# BlackIce.net
KiCad netlist of a schematic drawn in EAGLE
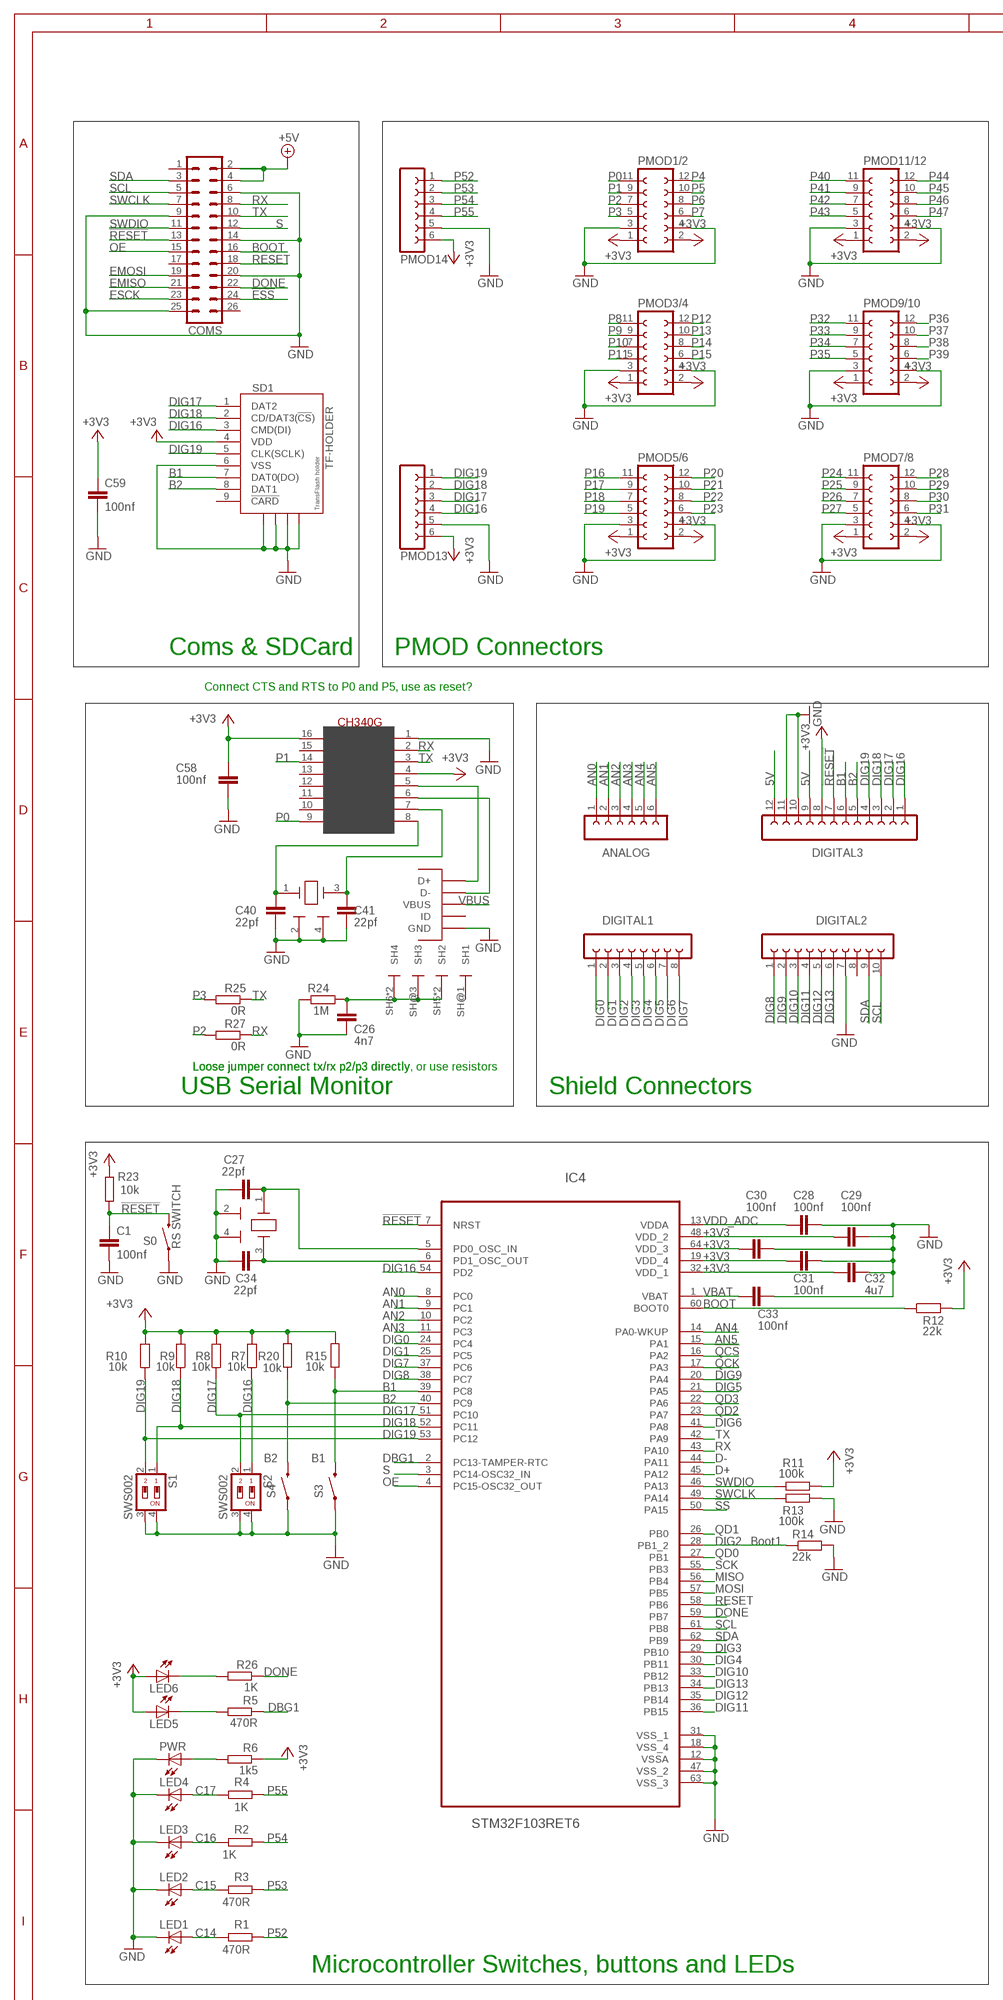
[diagram p0: schematic, sheet 1, part 1 of 2]
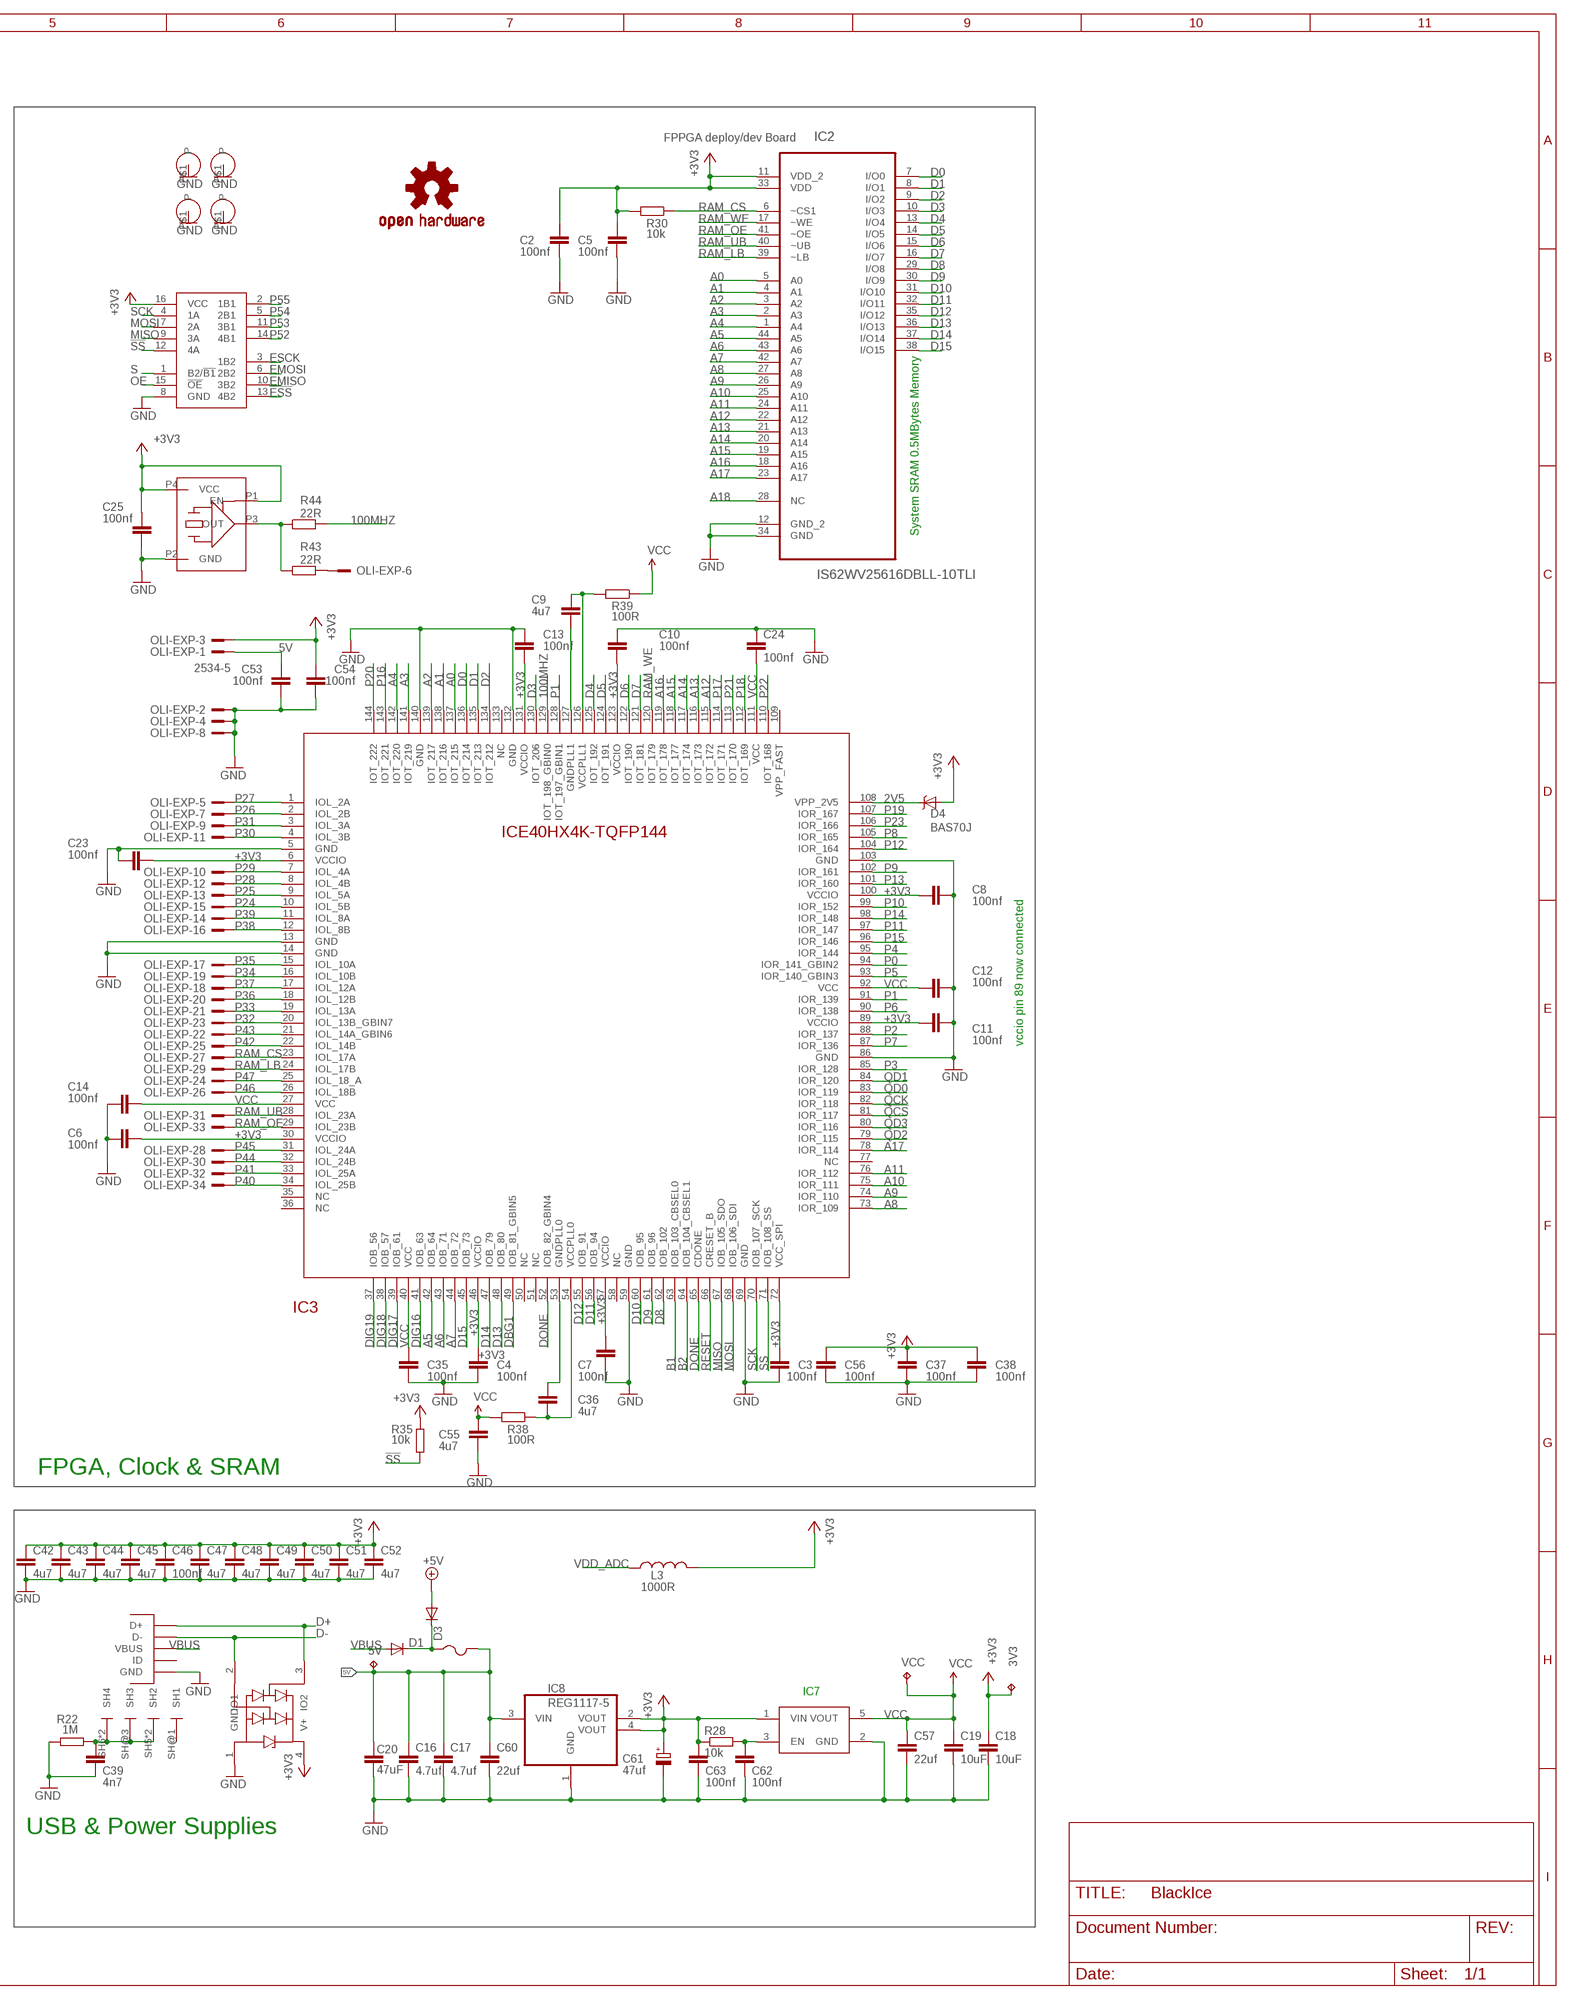
[diagram p1: schematic, sheet 1, part 2 of 2]

(export (version "E")
  (design (tool "Eeschema 10.0.6"))
  (components
    (comp (ref "3V3")
      (value "TPB1,27")
      (footprint "eagle-import:B1,27")
      (libsource (lib "eagle-import") (part "TPB1,27"))
    )
    (comp (ref "5V")
      (value "TPB1,27")
      (footprint "eagle-import:B1,27")
      (libsource (lib "eagle-import") (part "TPB1,27"))
    )
    (comp (ref "ANALOG")
      (value "FE06-1")
      (footprint "eagle-import:FE06")
      (libsource (lib "eagle-import") (part "FE06-1"))
    )
    (comp (ref "C1")
      (value "100nf")
      (footprint "eagle-import:C0402")
      (libsource (lib "eagle-import") (part "C-EUC0402"))
    )
    (comp (ref "C2")
      (value "100nf")
      (footprint "eagle-import:C0402")
      (libsource (lib "eagle-import") (part "C-EUC0402"))
    )
    (comp (ref "C3")
      (value "100nf")
      (footprint "eagle-import:C0402")
      (libsource (lib "eagle-import") (part "C-EUC0402"))
    )
    (comp (ref "C4")
      (value "100nf")
      (footprint "eagle-import:C0402")
      (libsource (lib "eagle-import") (part "C-EUC0402"))
    )
    (comp (ref "C5")
      (value "100nf")
      (footprint "eagle-import:C0402")
      (libsource (lib "eagle-import") (part "C-EUC0402"))
    )
    (comp (ref "C6")
      (value "100nf")
      (footprint "eagle-import:C0402")
      (libsource (lib "eagle-import") (part "C-EUC0402"))
    )
    (comp (ref "C7")
      (value "100nf")
      (footprint "eagle-import:C0402")
      (libsource (lib "eagle-import") (part "C-EUC0402"))
    )
    (comp (ref "C8")
      (value "100nf")
      (footprint "eagle-import:C0402")
      (libsource (lib "eagle-import") (part "C-EUC0402"))
    )
    (comp (ref "C9")
      (value "4u7")
      (footprint "eagle-import:C0402")
      (libsource (lib "eagle-import") (part "C-EUC0402"))
    )
    (comp (ref "C10")
      (value "100nf")
      (footprint "eagle-import:C0402")
      (libsource (lib "eagle-import") (part "C-EUC0402"))
    )
    (comp (ref "C11")
      (value "100nf")
      (footprint "eagle-import:C0402")
      (libsource (lib "eagle-import") (part "C-EUC0402"))
    )
    (comp (ref "C12")
      (value "100nf")
      (footprint "eagle-import:C0402")
      (libsource (lib "eagle-import") (part "C-EUC0402"))
    )
    (comp (ref "C13")
      (value "100nf")
      (footprint "eagle-import:C0402")
      (libsource (lib "eagle-import") (part "C-EUC0402"))
    )
    (comp (ref "C14")
      (value "100nf")
      (footprint "eagle-import:C0402")
      (libsource (lib "eagle-import") (part "C-EUC0402"))
    )
    (comp (ref "C16")
      (value "4.7uf")
      (footprint "eagle-import:C0402")
      (libsource (lib "eagle-import") (part "C-EUC0402"))
    )
    (comp (ref "C17")
      (value "4.7uf")
      (footprint "eagle-import:C0402")
      (libsource (lib "eagle-import") (part "C-EUC0402"))
    )
    (comp (ref "C18")
      (value "10uF")
      (footprint "eagle-import:C0603")
      (libsource (lib "eagle-import") (part "C-EUC0603"))
    )
    (comp (ref "C19")
      (value "10uF")
      (footprint "eagle-import:C0603")
      (libsource (lib "eagle-import") (part "C-EUC0603"))
    )
    (comp (ref "C20")
      (value "47uF")
      (footprint "eagle-import:1206")
      (libsource (lib "eagle-import") (part "C_1206"))
    )
    (comp (ref "C23")
      (value "100nf")
      (footprint "eagle-import:C0402")
      (libsource (lib "eagle-import") (part "C-EUC0402"))
    )
    (comp (ref "C24")
      (value "100nf")
      (footprint "eagle-import:C0402")
      (libsource (lib "eagle-import") (part "C-EUC0402"))
    )
    (comp (ref "C25")
      (value "100nf")
      (footprint "eagle-import:C0402")
      (libsource (lib "eagle-import") (part "C-EUC0402"))
    )
    (comp (ref "C26")
      (value "4n7")
      (footprint "eagle-import:C0402")
      (libsource (lib "eagle-import") (part "C-EUC0402"))
    )
    (comp (ref "C27")
      (value "22pf")
      (footprint "eagle-import:C0402")
      (libsource (lib "eagle-import") (part "C-EUC0402"))
    )
    (comp (ref "C28")
      (value "100nf")
      (footprint "eagle-import:C0402")
      (libsource (lib "eagle-import") (part "C-EUC0402"))
    )
    (comp (ref "C29")
      (value "100nf")
      (footprint "eagle-import:C0402")
      (libsource (lib "eagle-import") (part "C-EUC0402"))
    )
    (comp (ref "C30")
      (value "100nf")
      (footprint "eagle-import:C0402")
      (libsource (lib "eagle-import") (part "C-EUC0402"))
    )
    (comp (ref "C31")
      (value "100nf")
      (footprint "eagle-import:C0402")
      (libsource (lib "eagle-import") (part "C-EUC0402"))
    )
    (comp (ref "C32")
      (value "4u7")
      (footprint "eagle-import:C0402")
      (libsource (lib "eagle-import") (part "C-EUC0402"))
    )
    (comp (ref "C33")
      (value "100nf")
      (footprint "eagle-import:C0402")
      (libsource (lib "eagle-import") (part "C-EUC0402"))
    )
    (comp (ref "C34")
      (value "22pf")
      (footprint "eagle-import:C0402")
      (libsource (lib "eagle-import") (part "C-EUC0402"))
    )
    (comp (ref "C35")
      (value "100nf")
      (footprint "eagle-import:C0402")
      (libsource (lib "eagle-import") (part "C-EUC0402"))
    )
    (comp (ref "C36")
      (value "4u7")
      (footprint "eagle-import:C0402")
      (libsource (lib "eagle-import") (part "C-EUC0402"))
    )
    (comp (ref "C37")
      (value "100nf")
      (footprint "eagle-import:C0402")
      (libsource (lib "eagle-import") (part "C-EUC0402"))
    )
    (comp (ref "C38")
      (value "100nf")
      (footprint "eagle-import:C0402")
      (libsource (lib "eagle-import") (part "C-EUC0402"))
    )
    (comp (ref "C39")
      (value "4n7")
      (footprint "eagle-import:C0402")
      (libsource (lib "eagle-import") (part "C-EUC0402"))
    )
    (comp (ref "C40")
      (value "22pf")
      (footprint "eagle-import:C0402")
      (libsource (lib "eagle-import") (part "C-EUC0402"))
    )
    (comp (ref "C41")
      (value "22pf")
      (footprint "eagle-import:C0402")
      (libsource (lib "eagle-import") (part "C-EUC0402"))
    )
    (comp (ref "C42")
      (value "4u7")
      (footprint "eagle-import:C0402")
      (libsource (lib "eagle-import") (part "C-EUC0402"))
    )
    (comp (ref "C43")
      (value "4u7")
      (footprint "eagle-import:C0402")
      (libsource (lib "eagle-import") (part "C-EUC0402"))
    )
    (comp (ref "C44")
      (value "4u7")
      (footprint "eagle-import:C0402")
      (libsource (lib "eagle-import") (part "C-EUC0402"))
    )
    (comp (ref "C45")
      (value "4u7")
      (footprint "eagle-import:C0402")
      (libsource (lib "eagle-import") (part "C-EUC0402"))
    )
    (comp (ref "C46")
      (value "100nf")
      (footprint "eagle-import:C0402")
      (libsource (lib "eagle-import") (part "C-EUC0402"))
    )
    (comp (ref "C47")
      (value "4u7")
      (footprint "eagle-import:C0402")
      (libsource (lib "eagle-import") (part "C-EUC0402"))
    )
    (comp (ref "C48")
      (value "4u7")
      (footprint "eagle-import:C0402")
      (libsource (lib "eagle-import") (part "C-EUC0402"))
    )
    (comp (ref "C49")
      (value "4u7")
      (footprint "eagle-import:C0402")
      (libsource (lib "eagle-import") (part "C-EUC0402"))
    )
    (comp (ref "C50")
      (value "4u7")
      (footprint "eagle-import:C0402")
      (libsource (lib "eagle-import") (part "C-EUC0402"))
    )
    (comp (ref "C51")
      (value "4u7")
      (footprint "eagle-import:C0402")
      (libsource (lib "eagle-import") (part "C-EUC0402"))
    )
    (comp (ref "C52")
      (value "4u7")
      (footprint "eagle-import:C0402")
      (libsource (lib "eagle-import") (part "C-EUC0402"))
    )
    (comp (ref "C53")
      (value "100nf")
      (footprint "eagle-import:C0402")
      (libsource (lib "eagle-import") (part "C-EUC0402"))
    )
    (comp (ref "C54")
      (value "100nf")
      (footprint "eagle-import:C0402")
      (libsource (lib "eagle-import") (part "C-EUC0402"))
    )
    (comp (ref "C55")
      (value "4u7")
      (footprint "eagle-import:C0402")
      (libsource (lib "eagle-import") (part "C-EUC0402"))
    )
    (comp (ref "C56")
      (value "100nf")
      (footprint "eagle-import:C0402")
      (libsource (lib "eagle-import") (part "C-EUC0402"))
    )
    (comp (ref "C57")
      (value "22uf")
      (footprint "eagle-import:C0603")
      (libsource (lib "eagle-import") (part "C-EUC0603"))
    )
    (comp (ref "C58")
      (value "100nf")
      (footprint "eagle-import:C0402")
      (libsource (lib "eagle-import") (part "C-EUC0402"))
    )
    (comp (ref "C59")
      (value "100nf")
      (footprint "eagle-import:C0402")
      (libsource (lib "eagle-import") (part "C-EUC0402"))
    )
    (comp (ref "C60")
      (value "22uf")
      (footprint "eagle-import:C0603")
      (libsource (lib "eagle-import") (part "C-EUC0603"))
    )
    (comp (ref "C61")
      (value "47uf")
      (footprint "eagle-import:R_2012-12W")
      (libsource (lib "eagle-import") (part "CPOL-EUR/2012-12W"))
    )
    (comp (ref "C62")
      (value "100nf")
      (footprint "eagle-import:C0402")
      (libsource (lib "eagle-import") (part "C-EUC0402"))
    )
    (comp (ref "C63")
      (value "100nf")
      (footprint "eagle-import:C0402")
      (libsource (lib "eagle-import") (part "C-EUC0402"))
    )
    (comp (ref "COM")
      (value "FCI-MICROUSB-B-PEG")
      (footprint "eagle-import:MICROUSB-B-PEG")
      (libsource (lib "eagle-import") (part "FCI-MICROUSB-B-PEG"))
    )
    (comp (ref "COMS")
      (value "MA13-2")
      (footprint "eagle-import:MA13-2")
      (libsource (lib "eagle-import") (part "MA13-2"))
    )
    (comp (ref "D1")
      (value "DIODE-SOD123")
      (footprint "eagle-import:SOD123")
      (libsource (lib "eagle-import") (part "DIODE-SOD123"))
    )
    (comp (ref "D3")
      (value "DIODE-SOD123")
      (footprint "eagle-import:SOD123")
      (libsource (lib "eagle-import") (part "DIODE-SOD123"))
    )
    (comp (ref "D4")
      (value "BAS70J")
      (footprint "eagle-import:SOD-323")
      (libsource (lib "eagle-import") (part "BAS70J"))
    )
    (comp (ref "DIGITAL1")
      (value "FE08-1")
      (footprint "eagle-import:FE08")
      (libsource (lib "eagle-import") (part "FE08-1"))
    )
    (comp (ref "DIGITAL2")
      (value "FE10-1")
      (footprint "eagle-import:FE10")
      (libsource (lib "eagle-import") (part "FE10-1"))
    )
    (comp (ref "DIGITAL3")
      (value "FE12-1")
      (footprint "eagle-import:FE12")
      (libsource (lib "eagle-import") (part "FE12-1"))
    )
    (comp (ref "ESD1")
      (value "PRTR5V0U2X")
      (footprint "eagle-import:SOT143B")
      (libsource (lib "eagle-import") (part "PRTR5V0U2X"))
    )
    (comp (ref "F1")
      (value "PTCFUSE-1206")
      (footprint "eagle-import:R1206")
      (libsource (lib "eagle-import") (part "PTCFUSE-1206"))
    )
    (comp (ref "IC1")
      (value "CH340G")
      (footprint "eagle-import:SOIC16")
      (libsource (lib "eagle-import") (part "CH340G"))
    )
    (comp (ref "IC2")
      (value "IS62WV25616DBLL-10TLI")
      (footprint "eagle-import:SOP80P1176X120-44N")
      (fields (field (name "MPN") "IS62WV25616DBLL-45TLI"))
      (libsource (lib "eagle-import") (part "IS62WV25616DBLL-45TLI"))
    )
    (comp (ref "IC3")
      (value "ICE40HX4K_TQFP144")
      (footprint "eagle-import:TQFP144")
      (libsource (lib "eagle-import") (part "ICE40HX4K_TQFP144"))
    )
    (comp (ref "IC4")
      (value "STM32F103RET6")
      (footprint "eagle-import:QFP50P1200X1200X160-64N")
      (libsource (lib "eagle-import") (part "STM32F103RET6"))
    )
    (comp (ref "IC6")
      (value "74CBTLV3257")
      (footprint "eagle-import:TSSOP-16")
      (libsource (lib "eagle-import") (part "74CBTLV3257"))
    )
    (comp (ref "IC7")
      (value "NCP114")
      (footprint "eagle-import:TSOP-5_SOT23-5")
      (libsource (lib "eagle-import") (part "NCP114"))
    )
    (comp (ref "IC8")
      (value "REG1117-5")
      (footprint "eagle-import:SOT223")
      (libsource (lib "eagle-import") (part "REG1117-5"))
    )
    (comp (ref "L3")
      (value "1000R")
      (footprint "eagle-import:C0402")
      (libsource (lib "eagle-import") (part "INDUCTOR0402"))
    )
    (comp (ref "LED1")
      (value "LEDCHIPLED_0603")
      (footprint "eagle-import:CHIPLED_0603")
      (libsource (lib "eagle-import") (part "LEDCHIPLED_0603"))
    )
    (comp (ref "LED2")
      (value "LEDCHIPLED_0603")
      (footprint "eagle-import:CHIPLED_0603")
      (libsource (lib "eagle-import") (part "LEDCHIPLED_0603"))
    )
    (comp (ref "LED3")
      (value "LEDCHIPLED_0603")
      (footprint "eagle-import:CHIPLED_0603")
      (libsource (lib "eagle-import") (part "LEDCHIPLED_0603"))
    )
    (comp (ref "LED4")
      (value "LEDCHIPLED_0603")
      (footprint "eagle-import:CHIPLED_0603")
      (libsource (lib "eagle-import") (part "LEDCHIPLED_0603"))
    )
    (comp (ref "LED5")
      (value "LEDCHIPLED_0603")
      (footprint "eagle-import:CHIPLED_0603")
      (libsource (lib "eagle-import") (part "LEDCHIPLED_0603"))
    )
    (comp (ref "LED6")
      (value "LEDCHIPLED_0603")
      (footprint "eagle-import:CHIPLED_0603")
      (libsource (lib "eagle-import") (part "LEDCHIPLED_0603"))
    )
    (comp (ref "OLI-EXP")
      (value "2534-5")
      (footprint "eagle-import:PAK100_2500-5-34")
      (libsource (lib "eagle-import") (part "2534-5"))
    )
    (comp (ref "OSHW")
      (value "OSHW-LOGOL")
      (footprint "eagle-import:OSHW-LOGO-L")
      (libsource (lib "eagle-import") (part "OSHW-LOGOL"))
    )
    (comp (ref "PMOD1/2")
      (value "FE06-2W")
      (footprint "eagle-import:FE06-2W")
      (libsource (lib "eagle-import") (part "FE06-2W"))
    )
    (comp (ref "PMOD3/4")
      (value "FE06-2W")
      (footprint "eagle-import:FE06-2W")
      (libsource (lib "eagle-import") (part "FE06-2W"))
    )
    (comp (ref "PMOD5/6")
      (value "FE06-2W")
      (footprint "eagle-import:FE06-2W")
      (libsource (lib "eagle-import") (part "FE06-2W"))
    )
    (comp (ref "PMOD7/8")
      (value "FE06-2W")
      (footprint "eagle-import:FE06-2W")
      (libsource (lib "eagle-import") (part "FE06-2W"))
    )
    (comp (ref "PMOD9/10")
      (value "FE06-2W")
      (footprint "eagle-import:FE06-2W")
      (libsource (lib "eagle-import") (part "FE06-2W"))
    )
    (comp (ref "PMOD11/12")
      (value "FE06-2W")
      (footprint "eagle-import:FE06-2W")
      (libsource (lib "eagle-import") (part "FE06-2W"))
    )
    (comp (ref "PMOD13")
      (value "FE06W")
      (footprint "eagle-import:FE06W")
      (libsource (lib "eagle-import") (part "FE06W"))
    )
    (comp (ref "PMOD14")
      (value "FE06W")
      (footprint "eagle-import:FE06W")
      (libsource (lib "eagle-import") (part "FE06W"))
    )
    (comp (ref "PWR")
      (value "LEDCHIPLED_0603")
      (footprint "eagle-import:CHIPLED_0603")
      (libsource (lib "eagle-import") (part "LEDCHIPLED_0603"))
    )
    (comp (ref "R1")
      (value "470R")
      (footprint "eagle-import:R0402")
      (libsource (lib "eagle-import") (part "resistor_R-EU_R0402"))
    )
    (comp (ref "R2")
      (value "1K")
      (footprint "eagle-import:R0402")
      (libsource (lib "eagle-import") (part "resistor_R-EU_R0402"))
    )
    (comp (ref "R3")
      (value "470R")
      (footprint "eagle-import:R0402")
      (libsource (lib "eagle-import") (part "resistor_R-EU_R0402"))
    )
    (comp (ref "R4")
      (value "1K")
      (footprint "eagle-import:R0402")
      (libsource (lib "eagle-import") (part "resistor_R-EU_R0402"))
    )
    (comp (ref "R5")
      (value "470R")
      (footprint "eagle-import:R0402")
      (libsource (lib "eagle-import") (part "resistor_R-EU_R0402"))
    )
    (comp (ref "R6")
      (value "1k5")
      (footprint "eagle-import:R0402")
      (libsource (lib "eagle-import") (part "resistor_R-EU_R0402"))
    )
    (comp (ref "R7")
      (value "10k")
      (footprint "eagle-import:R0402")
      (libsource (lib "eagle-import") (part "resistor_R-EU_R0402"))
    )
    (comp (ref "R8")
      (value "10k")
      (footprint "eagle-import:R0402")
      (libsource (lib "eagle-import") (part "resistor_R-EU_R0402"))
    )
    (comp (ref "R9")
      (value "10k")
      (footprint "eagle-import:R0402")
      (libsource (lib "eagle-import") (part "resistor_R-EU_R0402"))
    )
    (comp (ref "R10")
      (value "10k")
      (footprint "eagle-import:R0402")
      (libsource (lib "eagle-import") (part "resistor_R-EU_R0402"))
    )
    (comp (ref "R11")
      (value "100k")
      (footprint "eagle-import:R0402")
      (libsource (lib "eagle-import") (part "resistor_R-EU_R0402"))
    )
    (comp (ref "R12")
      (value "22k")
      (footprint "eagle-import:R0402")
      (libsource (lib "eagle-import") (part "resistor_R-EU_R0402"))
    )
    (comp (ref "R13")
      (value "100k")
      (footprint "eagle-import:R0402")
      (libsource (lib "eagle-import") (part "resistor_R-EU_R0402"))
    )
    (comp (ref "R14")
      (value "22k")
      (footprint "eagle-import:R0402")
      (libsource (lib "eagle-import") (part "resistor_R-EU_R0402"))
    )
    (comp (ref "R15")
      (value "10k")
      (footprint "eagle-import:R0402")
      (libsource (lib "eagle-import") (part "resistor_R-EU_R0402"))
    )
    (comp (ref "R20")
      (value "10k")
      (footprint "eagle-import:R0402")
      (libsource (lib "eagle-import") (part "resistor_R-EU_R0402"))
    )
    (comp (ref "R22")
      (value "1M")
      (footprint "eagle-import:R0402")
      (libsource (lib "eagle-import") (part "resistor_R-EU_R0402"))
    )
    (comp (ref "R23")
      (value "10k")
      (footprint "eagle-import:R0402")
      (libsource (lib "eagle-import") (part "R-EU_R0402"))
    )
    (comp (ref "R24")
      (value "1M")
      (footprint "eagle-import:R0402")
      (libsource (lib "eagle-import") (part "resistor_R-EU_R0402"))
    )
    (comp (ref "R25")
      (value "0R")
      (footprint "eagle-import:R0402")
      (libsource (lib "eagle-import") (part "resistor_R-EU_R0402"))
    )
    (comp (ref "R26")
      (value "1K")
      (footprint "eagle-import:R0402")
      (libsource (lib "eagle-import") (part "resistor_R-EU_R0402"))
    )
    (comp (ref "R27")
      (value "0R")
      (footprint "eagle-import:R0402")
      (libsource (lib "eagle-import") (part "resistor_R-EU_R0402"))
    )
    (comp (ref "R28")
      (value "10k")
      (footprint "eagle-import:R0402")
      (libsource (lib "eagle-import") (part "resistor_R-EU_R0402"))
    )
    (comp (ref "R30")
      (value "10k")
      (footprint "eagle-import:R0402")
      (libsource (lib "eagle-import") (part "resistor_R-EU_R0402"))
    )
    (comp (ref "R35")
      (value "10k")
      (footprint "eagle-import:R0402")
      (libsource (lib "eagle-import") (part "resistor_R-EU_R0402"))
    )
    (comp (ref "R38")
      (value "100R")
      (footprint "eagle-import:R0402")
      (libsource (lib "eagle-import") (part "resistor_R-EU_R0402"))
    )
    (comp (ref "R39")
      (value "100R")
      (footprint "eagle-import:R0402")
      (libsource (lib "eagle-import") (part "resistor_R-EU_R0402"))
    )
    (comp (ref "R43")
      (value "22R")
      (footprint "eagle-import:R0402")
      (libsource (lib "eagle-import") (part "resistor_R-EU_R0402"))
    )
    (comp (ref "R44")
      (value "22R")
      (footprint "eagle-import:R0402")
      (libsource (lib "eagle-import") (part "resistor_R-EU_R0402"))
    )
    (comp (ref "S0")
      (value "RS SWITCH")
      (footprint "eagle-import:TACTILE-SWITCH-1101NE")
      (libsource (lib "eagle-import") (part "SWITCH-MOMENTARY-2SMD-1101NE"))
    )
    (comp (ref "S1")
      (value "SWS002")
      (footprint "eagle-import:SMS-002")
      (libsource (lib "eagle-import") (part "SWS002"))
    )
    (comp (ref "S2")
      (value "SWS002")
      (footprint "eagle-import:SMS-002")
      (libsource (lib "eagle-import") (part "SWS002"))
    )
    (comp (ref "S3")
      (value "SWITCH-MOMENTARY-2SMD-1101NE")
      (footprint "eagle-import:TACTILE-SWITCH-1101NE")
      (libsource (lib "eagle-import") (part "SWITCH-MOMENTARY-2SMD-1101NE"))
    )
    (comp (ref "S4")
      (value "SWITCH-MOMENTARY-2SMD-1101NE")
      (footprint "eagle-import:TACTILE-SWITCH-1101NE")
      (libsource (lib "eagle-import") (part "SWITCH-MOMENTARY-2SMD-1101NE"))
    )
    (comp (ref "SD1")
      (value "TF-HOLDER")
      (footprint "eagle-import:TF-PULL")
      (libsource (lib "eagle-import") (part "TF-HOLDER"))
    )
    (comp (ref "U$2")
      (value "FCI-MICROUSB-B-PEG")
      (footprint "eagle-import:MICROUSB-B-PEG")
      (libsource (lib "eagle-import") (part "FCI-MICROUSB-B-PEG"))
    )
    (comp (ref "U$16")
      (value "HOLE-2.5MM")
      (footprint "eagle-import:2.5MM-HOLE")
      (libsource (lib "eagle-import") (part "HOLE-2.5MM"))
    )
    (comp (ref "U$21")
      (value "HOLE-2.5MM")
      (footprint "eagle-import:2.5MM-HOLE")
      (libsource (lib "eagle-import") (part "HOLE-2.5MM"))
    )
    (comp (ref "U$22")
      (value "HOLE-2.5MM")
      (footprint "eagle-import:2.5MM-HOLE")
      (libsource (lib "eagle-import") (part "HOLE-2.5MM"))
    )
    (comp (ref "U$24")
      (value "HOLE-2.5MM")
      (footprint "eagle-import:2.5MM-HOLE")
      (libsource (lib "eagle-import") (part "HOLE-2.5MM"))
    )
    (comp (ref "VCC")
      (value "TPB1,27")
      (footprint "eagle-import:B1,27")
      (libsource (lib "eagle-import") (part "TPB1,27"))
    )
    (comp (ref "X1")
      (value "TXC-7W-20.000MBB-T")
      (footprint "eagle-import:XTAL-7X5")
      (libsource (lib "eagle-import") (part "TXC-7W-20.000MBB-T"))
    )
    (comp (ref "Y1")
      (value "12MZ")
      (footprint "eagle-import:CRYSTAL-3.2X2.5")
      (libsource (lib "eagle-import") (part "7M-25"))
    )
    (comp (ref "Y2")
      (value "12Mz")
      (footprint "eagle-import:CRYSTAL-3.2X2.5")
      (libsource (lib "eagle-import") (part "7M-25"))
    )
  )
  (nets
    (net (code "1") (name "+3V3") (class "Default")
      (node (ref "3V3") (pin "TP") (pinfunction "TP_TP") (pintype "input"))
      (node (ref "C10") (pin "2") (pinfunction "2_2") (pintype "passive"))
      (node (ref "C11") (pin "1") (pinfunction "1_1") (pintype "passive"))
      (node (ref "C13") (pin "1") (pinfunction "1_1") (pintype "passive"))
      (node (ref "C18") (pin "1") (pinfunction "1_1") (pintype "passive"))
      (node (ref "C2") (pin "1") (pinfunction "1_1") (pintype "passive"))
      (node (ref "C23") (pin "1") (pinfunction "1_1") (pintype "passive"))
      (node (ref "C25") (pin "2") (pinfunction "2_2") (pintype "passive"))
      (node (ref "C29") (pin "2") (pinfunction "2_2") (pintype "passive"))
      (node (ref "C3") (pin "1") (pinfunction "1_1") (pintype "passive"))
      (node (ref "C30") (pin "2") (pinfunction "2_2") (pintype "passive"))
      (node (ref "C31") (pin "2") (pinfunction "2_2") (pintype "passive"))
      (node (ref "C32") (pin "2") (pinfunction "2_2") (pintype "passive"))
      (node (ref "C37") (pin "1") (pinfunction "1_1") (pintype "passive"))
      (node (ref "C38") (pin "1") (pinfunction "1_1") (pintype "passive"))
      (node (ref "C4") (pin "1") (pinfunction "1_1") (pintype "passive"))
      (node (ref "C42") (pin "1") (pinfunction "1_1") (pintype "passive"))
      (node (ref "C43") (pin "1") (pinfunction "1_1") (pintype "passive"))
      (node (ref "C44") (pin "1") (pinfunction "1_1") (pintype "passive"))
      (node (ref "C45") (pin "1") (pinfunction "1_1") (pintype "passive"))
      (node (ref "C46") (pin "1") (pinfunction "1_1") (pintype "passive"))
      (node (ref "C47") (pin "1") (pinfunction "1_1") (pintype "passive"))
      (node (ref "C48") (pin "1") (pinfunction "1_1") (pintype "passive"))
      (node (ref "C49") (pin "1") (pinfunction "1_1") (pintype "passive"))
      (node (ref "C5") (pin "1") (pinfunction "1_1") (pintype "passive"))
      (node (ref "C50") (pin "1") (pinfunction "1_1") (pintype "passive"))
      (node (ref "C51") (pin "1") (pinfunction "1_1") (pintype "passive"))
      (node (ref "C52") (pin "1") (pinfunction "1_1") (pintype "passive"))
      (node (ref "C54") (pin "1") (pinfunction "1_1") (pintype "passive"))
      (node (ref "C56") (pin "1") (pinfunction "1_1") (pintype "passive"))
      (node (ref "C58") (pin "2") (pinfunction "2_2") (pintype "passive"))
      (node (ref "C59") (pin "1") (pinfunction "1_1") (pintype "passive"))
      (node (ref "C6") (pin "2") (pinfunction "2_2") (pintype "passive"))
      (node (ref "C61") (pin "+") (pinfunction "+_+") (pintype "passive"))
      (node (ref "C63") (pin "2") (pinfunction "2_2") (pintype "passive"))
      (node (ref "C7") (pin "1") (pinfunction "1_1") (pintype "passive"))
      (node (ref "C8") (pin "1") (pinfunction "1_1") (pintype "passive"))
      (node (ref "D4") (pin "A") (pinfunction "A_A") (pintype "passive"))
      (node (ref "DIGITAL3") (pin "8") (pinfunction "8_8") (pintype "passive"))
      (node (ref "ESD1") (pin "4") (pinfunction "V+_4") (pintype "bidirectional"))
      (node (ref "IC1") (pin "16") (pinfunction "VCC_16") (pintype "bidirectional"))
      (node (ref "IC1") (pin "4") (pinfunction "V3_4") (pintype "bidirectional"))
      (node (ref "IC2") (pin "11") (pinfunction "VDD_2_11") (pintype "power_in"))
      (node (ref "IC2") (pin "33") (pinfunction "VDD_33") (pintype "power_in"))
      (node (ref "IC3") (pin "100") (pinfunction "VCCIO_100") (pintype "bidirectional"))
      (node (ref "IC3") (pin "123") (pinfunction "VCCIO_123") (pintype "bidirectional"))
      (node (ref "IC3") (pin "131") (pinfunction "VCCIO_131") (pintype "bidirectional"))
      (node (ref "IC3") (pin "30") (pinfunction "VCCIO_30") (pintype "bidirectional"))
      (node (ref "IC3") (pin "46") (pinfunction "VCCIO_46") (pintype "bidirectional"))
      (node (ref "IC3") (pin "57") (pinfunction "VCCIO_57") (pintype "bidirectional"))
      (node (ref "IC3") (pin "6") (pinfunction "VCCIO_6") (pintype "bidirectional"))
      (node (ref "IC3") (pin "72") (pinfunction "VCC_SPI_72") (pintype "bidirectional"))
      (node (ref "IC3") (pin "89") (pinfunction "VCCIO_89") (pintype "bidirectional"))
      (node (ref "IC4") (pin "19") (pinfunction "VDD_4_19") (pintype "power_in"))
      (node (ref "IC4") (pin "32") (pinfunction "VDD_1_32") (pintype "power_in"))
      (node (ref "IC4") (pin "48") (pinfunction "VDD_2_48") (pintype "power_in"))
      (node (ref "IC4") (pin "64") (pinfunction "VDD_3_64") (pintype "power_in"))
      (node (ref "IC6") (pin "16") (pinfunction "VCC_16") (pintype "power_in"))
      (node (ref "IC7") (pin "1") (pinfunction "VIN_1") (pintype "power_in"))
      (node (ref "IC8") (pin "2") (pinfunction "VOUT_2") (pintype "output"))
      (node (ref "IC8") (pin "4") (pinfunction "VOUT_4") (pintype "output"))
      (node (ref "L3") (pin "1") (pinfunction "1_1") (pintype "passive"))
      (node (ref "LED5") (pin "A") (pinfunction "A_A") (pintype "passive"))
      (node (ref "LED6") (pin "A") (pinfunction "A_A") (pintype "passive"))
      (node (ref "OLI-EXP") (pin "3") (pinfunction "KL_3") (pintype "passive"))
      (node (ref "PMOD1/2") (pin "1") (pinfunction "1_1") (pintype "passive"))
      (node (ref "PMOD1/2") (pin "2") (pinfunction "2_2") (pintype "passive"))
      (node (ref "PMOD11/12") (pin "1") (pinfunction "1_1") (pintype "passive"))
      (node (ref "PMOD11/12") (pin "2") (pinfunction "2_2") (pintype "passive"))
      (node (ref "PMOD13") (pin "6") (pinfunction "6_6") (pintype "passive"))
      (node (ref "PMOD14") (pin "6") (pinfunction "6_6") (pintype "passive"))
      (node (ref "PMOD3/4") (pin "1") (pinfunction "1_1") (pintype "passive"))
      (node (ref "PMOD3/4") (pin "2") (pinfunction "2_2") (pintype "passive"))
      (node (ref "PMOD5/6") (pin "1") (pinfunction "1_1") (pintype "passive"))
      (node (ref "PMOD5/6") (pin "2") (pinfunction "2_2") (pintype "passive"))
      (node (ref "PMOD7/8") (pin "1") (pinfunction "1_1") (pintype "passive"))
      (node (ref "PMOD7/8") (pin "2") (pinfunction "2_2") (pintype "passive"))
      (node (ref "PMOD9/10") (pin "1") (pinfunction "1_1") (pintype "passive"))
      (node (ref "PMOD9/10") (pin "2") (pinfunction "2_2") (pintype "passive"))
      (node (ref "R10") (pin "2") (pinfunction "2_2") (pintype "passive"))
      (node (ref "R11") (pin "1") (pinfunction "1_1") (pintype "passive"))
      (node (ref "R12") (pin "2") (pinfunction "2_2") (pintype "passive"))
      (node (ref "R15") (pin "2") (pinfunction "2_2") (pintype "passive"))
      (node (ref "R20") (pin "2") (pinfunction "2_2") (pintype "passive"))
      (node (ref "R23") (pin "2") (pinfunction "2_2") (pintype "passive"))
      (node (ref "R28") (pin "1") (pinfunction "1_1") (pintype "passive"))
      (node (ref "R30") (pin "2") (pinfunction "2_2") (pintype "passive"))
      (node (ref "R35") (pin "1") (pinfunction "1_1") (pintype "passive"))
      (node (ref "R6") (pin "1") (pinfunction "1_1") (pintype "passive"))
      (node (ref "R7") (pin "2") (pinfunction "2_2") (pintype "passive"))
      (node (ref "R8") (pin "2") (pinfunction "2_2") (pintype "passive"))
      (node (ref "R9") (pin "2") (pinfunction "2_2") (pintype "passive"))
      (node (ref "SD1") (pin "4") (pinfunction "VDD_4") (pintype "power_in"))
      (node (ref "X1") (pin "P1") (pinfunction "EN_P1") (pintype "input"))
      (node (ref "X1") (pin "P4") (pinfunction "VCC_P4") (pintype "power_in"))
    )
    (net (code "2") (name "+5V") (class "Default")
      (node (ref "COMS") (pin "2") (pinfunction "2_2") (pintype "passive"))
      (node (ref "COMS") (pin "4") (pinfunction "4_4") (pintype "passive"))
      (node (ref "D3") (pin "A") (pinfunction "A_A") (pintype "passive"))
    )
    (net (code "3") (name "/2V5") (class "Default")
      (node (ref "D4") (pin "C") (pinfunction "C_C") (pintype "passive"))
      (node (ref "IC3") (pin "108") (pinfunction "VPP_2V5_108") (pintype "bidirectional"))
    )
    (net (code "4") (name "/100MHZ") (class "Default")
      (node (ref "IC3") (pin "129") (pinfunction "IOT_198_GBIN0_129") (pintype "bidirectional"))
      (node (ref "R44") (pin "2") (pinfunction "2_2") (pintype "passive"))
    )
    (net (code "5") (name "/A0") (class "Default")
      (node (ref "IC2") (pin "5") (pinfunction "A0_5") (pintype "input"))
      (node (ref "IC3") (pin "137") (pinfunction "IOT_215_137") (pintype "bidirectional"))
    )
    (net (code "6") (name "/A1") (class "Default")
      (node (ref "IC2") (pin "4") (pinfunction "A1_4") (pintype "input"))
      (node (ref "IC3") (pin "138") (pinfunction "IOT_216_138") (pintype "bidirectional"))
    )
    (net (code "7") (name "/A2") (class "Default")
      (node (ref "IC2") (pin "3") (pinfunction "A2_3") (pintype "input"))
      (node (ref "IC3") (pin "139") (pinfunction "IOT_217_139") (pintype "bidirectional"))
    )
    (net (code "8") (name "/A3") (class "Default")
      (node (ref "IC2") (pin "2") (pinfunction "A3_2") (pintype "input"))
      (node (ref "IC3") (pin "141") (pinfunction "IOT_219_141") (pintype "bidirectional"))
    )
    (net (code "9") (name "/A4") (class "Default")
      (node (ref "IC2") (pin "1") (pinfunction "A4_1") (pintype "input"))
      (node (ref "IC3") (pin "142") (pinfunction "IOT_220_142") (pintype "bidirectional"))
    )
    (net (code "10") (name "/A5") (class "Default")
      (node (ref "IC2") (pin "44") (pinfunction "A5_44") (pintype "input"))
      (node (ref "IC3") (pin "42") (pinfunction "IOB_64_42") (pintype "bidirectional"))
    )
    (net (code "11") (name "/A6") (class "Default")
      (node (ref "IC2") (pin "43") (pinfunction "A6_43") (pintype "input"))
      (node (ref "IC3") (pin "43") (pinfunction "IOB_71_43") (pintype "bidirectional"))
    )
    (net (code "12") (name "/A7") (class "Default")
      (node (ref "IC2") (pin "42") (pinfunction "A7_42") (pintype "input"))
      (node (ref "IC3") (pin "44") (pinfunction "IOB_72_44") (pintype "bidirectional"))
    )
    (net (code "13") (name "/A8") (class "Default")
      (node (ref "IC2") (pin "27") (pinfunction "A8_27") (pintype "input"))
      (node (ref "IC3") (pin "73") (pinfunction "IOR_109_73") (pintype "bidirectional"))
    )
    (net (code "14") (name "/A9") (class "Default")
      (node (ref "IC2") (pin "26") (pinfunction "A9_26") (pintype "input"))
      (node (ref "IC3") (pin "74") (pinfunction "IOR_110_74") (pintype "bidirectional"))
    )
    (net (code "15") (name "/A10") (class "Default")
      (node (ref "IC2") (pin "25") (pinfunction "A10_25") (pintype "input"))
      (node (ref "IC3") (pin "75") (pinfunction "IOR_111_75") (pintype "bidirectional"))
    )
    (net (code "16") (name "/A11") (class "Default")
      (node (ref "IC2") (pin "24") (pinfunction "A11_24") (pintype "input"))
      (node (ref "IC3") (pin "76") (pinfunction "IOR_112_76") (pintype "bidirectional"))
    )
    (net (code "17") (name "/A12") (class "Default")
      (node (ref "IC2") (pin "22") (pinfunction "A12_22") (pintype "input"))
      (node (ref "IC3") (pin "115") (pinfunction "IOT_172_115") (pintype "bidirectional"))
    )
    (net (code "18") (name "/A13") (class "Default")
      (node (ref "IC2") (pin "21") (pinfunction "A13_21") (pintype "input"))
      (node (ref "IC3") (pin "116") (pinfunction "IOT_173_116") (pintype "bidirectional"))
    )
    (net (code "19") (name "/A14") (class "Default")
      (node (ref "IC2") (pin "20") (pinfunction "A14_20") (pintype "input"))
      (node (ref "IC3") (pin "117") (pinfunction "IOT_174_117") (pintype "bidirectional"))
    )
    (net (code "20") (name "/A15") (class "Default")
      (node (ref "IC2") (pin "19") (pinfunction "A15_19") (pintype "input"))
      (node (ref "IC3") (pin "118") (pinfunction "IOT_177_118") (pintype "bidirectional"))
    )
    (net (code "21") (name "/A16") (class "Default")
      (node (ref "IC2") (pin "18") (pinfunction "A16_18") (pintype "input"))
      (node (ref "IC3") (pin "119") (pinfunction "IOT_178_119") (pintype "bidirectional"))
    )
    (net (code "22") (name "/A17") (class "Default")
      (node (ref "IC2") (pin "23") (pinfunction "A17_23") (pintype "input"))
      (node (ref "IC3") (pin "78") (pinfunction "IOR_114_78") (pintype "bidirectional"))
    )
    (net (code "24") (name "/AN0") (class "Default")
      (node (ref "ANALOG") (pin "1") (pinfunction "1_1") (pintype "passive"))
      (node (ref "IC4") (pin "8") (pinfunction "PC0_8") (pintype "bidirectional"))
    )
    (net (code "25") (name "/AN1") (class "Default")
      (node (ref "ANALOG") (pin "2") (pinfunction "2_2") (pintype "passive"))
      (node (ref "IC4") (pin "9") (pinfunction "PC1_9") (pintype "bidirectional"))
    )
    (net (code "26") (name "/AN2") (class "Default")
      (node (ref "ANALOG") (pin "3") (pinfunction "3_3") (pintype "passive"))
      (node (ref "IC4") (pin "10") (pinfunction "PC2_10") (pintype "bidirectional"))
    )
    (net (code "27") (name "/AN3") (class "Default")
      (node (ref "ANALOG") (pin "4") (pinfunction "4_4") (pintype "passive"))
      (node (ref "IC4") (pin "11") (pinfunction "PC3_11") (pintype "bidirectional"))
    )
    (net (code "28") (name "/AN4") (class "Default")
      (node (ref "ANALOG") (pin "5") (pinfunction "5_5") (pintype "passive"))
      (node (ref "IC4") (pin "14") (pinfunction "PA0-WKUP_14") (pintype "bidirectional"))
    )
    (net (code "29") (name "/AN5") (class "Default")
      (node (ref "ANALOG") (pin "6") (pinfunction "6_6") (pintype "passive"))
      (node (ref "IC4") (pin "15") (pinfunction "PA1_15") (pintype "bidirectional"))
    )
    (net (code "30") (name "/B1") (class "Default")
      (node (ref "DIGITAL3") (pin "6") (pinfunction "6_6") (pintype "passive"))
      (node (ref "IC3") (pin "63") (pinfunction "IOB_103_CBSEL0_63") (pintype "bidirectional"))
      (node (ref "IC4") (pin "39") (pinfunction "PC8_39") (pintype "bidirectional"))
      (node (ref "R15") (pin "1") (pinfunction "1_1") (pintype "passive"))
      (node (ref "S3") (pin "2") (pinfunction "2_2") (pintype "passive"))
      (node (ref "SD1") (pin "7") (pinfunction "DAT0(DO)_7") (pintype "bidirectional"))
    )
    (net (code "31") (name "/B2") (class "Default")
      (node (ref "DIGITAL3") (pin "5") (pinfunction "5_5") (pintype "passive"))
      (node (ref "IC3") (pin "64") (pinfunction "IOB_104_CBSEL1_64") (pintype "bidirectional"))
      (node (ref "IC4") (pin "40") (pinfunction "PC9_40") (pintype "bidirectional"))
      (node (ref "R20") (pin "1") (pinfunction "1_1") (pintype "passive"))
      (node (ref "S4") (pin "2") (pinfunction "2_2") (pintype "passive"))
      (node (ref "SD1") (pin "8") (pinfunction "DAT1_8") (pintype "bidirectional"))
    )
    (net (code "32") (name "/BOOT") (class "Default")
      (node (ref "COMS") (pin "16") (pinfunction "16_16") (pintype "passive"))
      (node (ref "IC4") (pin "60") (pinfunction "BOOT0_60") (pintype "passive"))
      (node (ref "R12") (pin "1") (pinfunction "1_1") (pintype "passive"))
    )
    (net (code "33") (name "/C14") (class "Default")
      (node (ref "LED1") (pin "A") (pinfunction "A_A") (pintype "passive"))
      (node (ref "R1") (pin "1") (pinfunction "1_1") (pintype "passive"))
    )
    (net (code "34") (name "/C15") (class "Default")
      (node (ref "LED2") (pin "A") (pinfunction "A_A") (pintype "passive"))
      (node (ref "R3") (pin "1") (pinfunction "1_1") (pintype "passive"))
    )
    (net (code "35") (name "/C16") (class "Default")
      (node (ref "LED3") (pin "A") (pinfunction "A_A") (pintype "passive"))
      (node (ref "R2") (pin "1") (pinfunction "1_1") (pintype "passive"))
    )
    (net (code "36") (name "/C17") (class "Default")
      (node (ref "LED4") (pin "A") (pinfunction "A_A") (pintype "passive"))
      (node (ref "R4") (pin "1") (pinfunction "1_1") (pintype "passive"))
    )
    (net (code "37") (name "/D+") (class "Default")
      (node (ref "ESD1") (pin "3") (pinfunction "IO2_3") (pintype "bidirectional"))
      (node (ref "IC4") (pin "45") (pinfunction "PA12_45") (pintype "bidirectional"))
      (node (ref "U$2") (pin "P$3") (pinfunction "D+_P$3") (pintype "bidirectional"))
    )
    (net (code "38") (name "/D-") (class "Default")
      (node (ref "ESD1") (pin "2") (pinfunction "IO1_2") (pintype "bidirectional"))
      (node (ref "IC4") (pin "44") (pinfunction "PA11_44") (pintype "bidirectional"))
      (node (ref "U$2") (pin "P$2") (pinfunction "D-_P$2") (pintype "bidirectional"))
    )
    (net (code "39") (name "/D0") (class "Default")
      (node (ref "IC2") (pin "7") (pinfunction "I/O0_7") (pintype "bidirectional"))
      (node (ref "IC3") (pin "136") (pinfunction "IOT_214_136") (pintype "bidirectional"))
    )
    (net (code "40") (name "/D1") (class "Default")
      (node (ref "IC2") (pin "8") (pinfunction "I/O1_8") (pintype "bidirectional"))
      (node (ref "IC3") (pin "135") (pinfunction "IOT_213_135") (pintype "bidirectional"))
    )
    (net (code "41") (name "/D2") (class "Default")
      (node (ref "IC2") (pin "9") (pinfunction "I/O2_9") (pintype "bidirectional"))
      (node (ref "IC3") (pin "134") (pinfunction "IOT_212_134") (pintype "bidirectional"))
    )
    (net (code "42") (name "/D3") (class "Default")
      (node (ref "IC2") (pin "10") (pinfunction "I/O3_10") (pintype "bidirectional"))
      (node (ref "IC3") (pin "130") (pinfunction "IOT_206_130") (pintype "bidirectional"))
    )
    (net (code "43") (name "/D4") (class "Default")
      (node (ref "IC2") (pin "13") (pinfunction "I/O4_13") (pintype "bidirectional"))
      (node (ref "IC3") (pin "125") (pinfunction "IOT_192_125") (pintype "bidirectional"))
    )
    (net (code "44") (name "/D5") (class "Default")
      (node (ref "IC2") (pin "14") (pinfunction "I/O5_14") (pintype "bidirectional"))
      (node (ref "IC3") (pin "124") (pinfunction "IOT_191_124") (pintype "bidirectional"))
    )
    (net (code "45") (name "/D6") (class "Default")
      (node (ref "IC2") (pin "15") (pinfunction "I/O6_15") (pintype "bidirectional"))
      (node (ref "IC3") (pin "122") (pinfunction "IOT_190_122") (pintype "bidirectional"))
    )
    (net (code "46") (name "/D7") (class "Default")
      (node (ref "IC2") (pin "16") (pinfunction "I/O7_16") (pintype "bidirectional"))
      (node (ref "IC3") (pin "121") (pinfunction "IOT_181_121") (pintype "bidirectional"))
    )
    (net (code "47") (name "/D8") (class "Default")
      (node (ref "IC2") (pin "29") (pinfunction "I/O8_29") (pintype "bidirectional"))
      (node (ref "IC3") (pin "62") (pinfunction "IOB_102_62") (pintype "bidirectional"))
    )
    (net (code "48") (name "/D9") (class "Default")
      (node (ref "IC2") (pin "30") (pinfunction "I/O9_30") (pintype "bidirectional"))
      (node (ref "IC3") (pin "61") (pinfunction "IOB_96_61") (pintype "bidirectional"))
    )
    (net (code "49") (name "/D10") (class "Default")
      (node (ref "IC2") (pin "31") (pinfunction "I/O10_31") (pintype "bidirectional"))
      (node (ref "IC3") (pin "60") (pinfunction "IOB_95_60") (pintype "bidirectional"))
    )
    (net (code "50") (name "/D11") (class "Default")
      (node (ref "IC2") (pin "32") (pinfunction "I/O11_32") (pintype "bidirectional"))
      (node (ref "IC3") (pin "56") (pinfunction "IOB_94_56") (pintype "bidirectional"))
    )
    (net (code "51") (name "/D12") (class "Default")
      (node (ref "IC2") (pin "35") (pinfunction "I/O12_35") (pintype "bidirectional"))
      (node (ref "IC3") (pin "55") (pinfunction "IOB_91_55") (pintype "bidirectional"))
    )
    (net (code "52") (name "/D13") (class "Default")
      (node (ref "IC2") (pin "36") (pinfunction "I/O13_36") (pintype "bidirectional"))
      (node (ref "IC3") (pin "48") (pinfunction "IOB_80_48") (pintype "bidirectional"))
    )
    (net (code "53") (name "/D14") (class "Default")
      (node (ref "IC2") (pin "37") (pinfunction "I/O14_37") (pintype "bidirectional"))
      (node (ref "IC3") (pin "47") (pinfunction "IOB_79_47") (pintype "bidirectional"))
    )
    (net (code "54") (name "/D15") (class "Default")
      (node (ref "IC2") (pin "38") (pinfunction "I/O15_38") (pintype "bidirectional"))
      (node (ref "IC3") (pin "45") (pinfunction "IOB_73_45") (pintype "bidirectional"))
    )
    (net (code "55") (name "/DBG1") (class "Default")
      (node (ref "IC3") (pin "49") (pinfunction "IOB_81_GBIN5_49") (pintype "bidirectional"))
      (node (ref "IC4") (pin "2") (pinfunction "PC13-TAMPER-RTC_2") (pintype "input"))
      (node (ref "R5") (pin "1") (pinfunction "1_1") (pintype "passive"))
    )
    (net (code "56") (name "/DIG0") (class "Default")
      (node (ref "DIGITAL1") (pin "1") (pinfunction "1_1") (pintype "passive"))
      (node (ref "IC4") (pin "24") (pinfunction "PC4_24") (pintype "passive"))
    )
    (net (code "57") (name "/DIG1") (class "Default")
      (node (ref "DIGITAL1") (pin "2") (pinfunction "2_2") (pintype "passive"))
      (node (ref "IC4") (pin "25") (pinfunction "PC5_25") (pintype "bidirectional"))
    )
    (net (code "58") (name "/DIG2") (class "Default")
      (node (ref "DIGITAL1") (pin "3") (pinfunction "3_3") (pintype "passive"))
      (node (ref "IC4") (pin "28") (pinfunction "PB1_2_28") (pintype "bidirectional"))
      (node (ref "R14") (pin "1") (pinfunction "1_1") (pintype "passive"))
    )
    (net (code "59") (name "/DIG3") (class "Default")
      (node (ref "DIGITAL1") (pin "4") (pinfunction "4_4") (pintype "passive"))
      (node (ref "IC4") (pin "29") (pinfunction "PB10_29") (pintype "bidirectional"))
    )
    (net (code "60") (name "/DIG4") (class "Default")
      (node (ref "DIGITAL1") (pin "5") (pinfunction "5_5") (pintype "passive"))
      (node (ref "IC4") (pin "30") (pinfunction "PB11_30") (pintype "bidirectional"))
    )
    (net (code "61") (name "/DIG5") (class "Default")
      (node (ref "DIGITAL1") (pin "6") (pinfunction "6_6") (pintype "passive"))
      (node (ref "IC4") (pin "21") (pinfunction "PA5_21") (pintype "bidirectional"))
    )
    (net (code "62") (name "/DIG6") (class "Default")
      (node (ref "DIGITAL1") (pin "7") (pinfunction "7_7") (pintype "passive"))
      (node (ref "IC4") (pin "41") (pinfunction "PA8_41") (pintype "bidirectional"))
    )
    (net (code "63") (name "/DIG7") (class "Default")
      (node (ref "DIGITAL1") (pin "8") (pinfunction "8_8") (pintype "passive"))
      (node (ref "IC4") (pin "37") (pinfunction "PC6_37") (pintype "bidirectional"))
    )
    (net (code "64") (name "/DIG8") (class "Default")
      (node (ref "DIGITAL2") (pin "1") (pinfunction "1_1") (pintype "passive"))
      (node (ref "IC4") (pin "38") (pinfunction "PC7_38") (pintype "bidirectional"))
    )
    (net (code "65") (name "/DIG9") (class "Default")
      (node (ref "DIGITAL2") (pin "2") (pinfunction "2_2") (pintype "passive"))
      (node (ref "IC4") (pin "20") (pinfunction "PA4_20") (pintype "bidirectional"))
    )
    (net (code "66") (name "/DIG10") (class "Default")
      (node (ref "DIGITAL2") (pin "3") (pinfunction "3_3") (pintype "passive"))
      (node (ref "IC4") (pin "33") (pinfunction "PB12_33") (pintype "bidirectional"))
    )
    (net (code "67") (name "/DIG11") (class "Default")
      (node (ref "DIGITAL2") (pin "4") (pinfunction "4_4") (pintype "passive"))
      (node (ref "IC4") (pin "36") (pinfunction "PB15_36") (pintype "bidirectional"))
    )
    (net (code "68") (name "/DIG12") (class "Default")
      (node (ref "DIGITAL2") (pin "5") (pinfunction "5_5") (pintype "passive"))
      (node (ref "IC4") (pin "35") (pinfunction "PB14_35") (pintype "bidirectional"))
    )
    (net (code "69") (name "/DIG13") (class "Default")
      (node (ref "DIGITAL2") (pin "6") (pinfunction "6_6") (pintype "passive"))
      (node (ref "IC4") (pin "34") (pinfunction "PB13_34") (pintype "bidirectional"))
    )
    (net (code "70") (name "/DIG16") (class "Default")
      (node (ref "DIGITAL3") (pin "1") (pinfunction "1_1") (pintype "passive"))
      (node (ref "IC3") (pin "41") (pinfunction "IOB_63_41") (pintype "bidirectional"))
      (node (ref "IC4") (pin "54") (pinfunction "PD2_54") (pintype "bidirectional"))
      (node (ref "PMOD13") (pin "4") (pinfunction "4_4") (pintype "passive"))
      (node (ref "R7") (pin "1") (pinfunction "1_1") (pintype "passive"))
      (node (ref "S2") (pin "1") (pinfunction "1_1") (pintype "passive"))
      (node (ref "SD1") (pin "3") (pinfunction "CMD(DI)_3") (pintype "bidirectional"))
    )
    (net (code "71") (name "/DIG17") (class "Default")
      (node (ref "DIGITAL3") (pin "2") (pinfunction "2_2") (pintype "passive"))
      (node (ref "IC3") (pin "39") (pinfunction "IOB_61_39") (pintype "bidirectional"))
      (node (ref "IC4") (pin "51") (pinfunction "PC10_51") (pintype "bidirectional"))
      (node (ref "PMOD13") (pin "3") (pinfunction "3_3") (pintype "passive"))
      (node (ref "R8") (pin "1") (pinfunction "1_1") (pintype "passive"))
      (node (ref "S2") (pin "2") (pinfunction "2_2") (pintype "passive"))
      (node (ref "SD1") (pin "1") (pinfunction "DAT2_1") (pintype "bidirectional"))
    )
    (net (code "72") (name "/DIG18") (class "Default")
      (node (ref "DIGITAL3") (pin "3") (pinfunction "3_3") (pintype "passive"))
      (node (ref "IC3") (pin "38") (pinfunction "IOB_57_38") (pintype "bidirectional"))
      (node (ref "IC4") (pin "52") (pinfunction "PC11_52") (pintype "bidirectional"))
      (node (ref "PMOD13") (pin "2") (pinfunction "2_2") (pintype "passive"))
      (node (ref "R9") (pin "1") (pinfunction "1_1") (pintype "passive"))
      (node (ref "S1") (pin "1") (pinfunction "1_1") (pintype "passive"))
      (node (ref "SD1") (pin "2") (pinfunction "CD/DAT3(~{CS})_2") (pintype "bidirectional"))
    )
    (net (code "73") (name "/DIG19") (class "Default")
      (node (ref "DIGITAL3") (pin "4") (pinfunction "4_4") (pintype "passive"))
      (node (ref "IC3") (pin "37") (pinfunction "IOB_56_37") (pintype "bidirectional"))
      (node (ref "IC4") (pin "53") (pinfunction "PC12_53") (pintype "bidirectional"))
      (node (ref "PMOD13") (pin "1") (pinfunction "1_1") (pintype "passive"))
      (node (ref "R10") (pin "1") (pinfunction "1_1") (pintype "passive"))
      (node (ref "S1") (pin "2") (pinfunction "2_2") (pintype "passive"))
      (node (ref "SD1") (pin "5") (pinfunction "CLK(SCLK)_5") (pintype "input"))
    )
    (net (code "74") (name "/DONE") (class "Default")
      (node (ref "COMS") (pin "22") (pinfunction "22_22") (pintype "passive"))
      (node (ref "IC3") (pin "52") (pinfunction "IOB_82_GBIN4_52") (pintype "bidirectional"))
      (node (ref "IC3") (pin "65") (pinfunction "CDONE_65") (pintype "bidirectional"))
      (node (ref "IC4") (pin "59") (pinfunction "PB7_59") (pintype "power_in"))
      (node (ref "R26") (pin "1") (pinfunction "1_1") (pintype "passive"))
    )
    (net (code "75") (name "/EMISO") (class "Default")
      (node (ref "COMS") (pin "21") (pinfunction "21_21") (pintype "passive"))
      (node (ref "IC6") (pin "10") (pinfunction "3B2_10") (pintype "bidirectional"))
    )
    (net (code "76") (name "/EMOSI") (class "Default")
      (node (ref "COMS") (pin "19") (pinfunction "19_19") (pintype "passive"))
      (node (ref "IC6") (pin "6") (pinfunction "2B2_6") (pintype "bidirectional"))
    )
    (net (code "77") (name "/ESCK") (class "Default")
      (node (ref "COMS") (pin "23") (pinfunction "23_23") (pintype "passive"))
      (node (ref "IC6") (pin "3") (pinfunction "1B2_3") (pintype "bidirectional"))
    )
    (net (code "78") (name "/MISO") (class "Default")
      (node (ref "IC3") (pin "67") (pinfunction "IOB_105_SDO_67") (pintype "bidirectional"))
      (node (ref "IC4") (pin "56") (pinfunction "PB4_56") (pintype "bidirectional"))
      (node (ref "IC6") (pin "9") (pinfunction "3A_9") (pintype "bidirectional"))
    )
    (net (code "79") (name "/MOSI") (class "Default")
      (node (ref "IC3") (pin "68") (pinfunction "IOB_106_SDI_68") (pintype "bidirectional"))
      (node (ref "IC4") (pin "57") (pinfunction "PB5_57") (pintype "bidirectional"))
      (node (ref "IC6") (pin "7") (pinfunction "2A_7") (pintype "bidirectional"))
    )
    (net (code "80") (name "/OE") (class "Default")
      (node (ref "COMS") (pin "15") (pinfunction "15_15") (pintype "passive"))
      (node (ref "IC4") (pin "4") (pinfunction "PC15-OSC32_OUT_4") (pintype "output"))
      (node (ref "IC6") (pin "15") (pinfunction "~{OE}_15") (pintype "bidirectional"))
    )
    (net (code "81") (name "/P0") (class "Default")
      (node (ref "IC1") (pin "9") (pinfunction "CTS_9") (pintype "bidirectional"))
      (node (ref "IC3") (pin "94") (pinfunction "IOR_141_GBIN2_94") (pintype "bidirectional"))
      (node (ref "PMOD1/2") (pin "11") (pinfunction "11_11") (pintype "passive"))
    )
    (net (code "82") (name "/P1") (class "Default")
      (node (ref "IC1") (pin "14") (pinfunction "RTS_14") (pintype "bidirectional"))
      (node (ref "IC3") (pin "128") (pinfunction "IOT_197_GBIN1_128") (pintype "bidirectional"))
      (node (ref "IC3") (pin "91") (pinfunction "IOR_139_91") (pintype "bidirectional"))
      (node (ref "PMOD1/2") (pin "9") (pinfunction "9_9") (pintype "passive"))
    )
    (net (code "83") (name "/P2") (class "Default")
      (node (ref "IC3") (pin "88") (pinfunction "IOR_137_88") (pintype "bidirectional"))
      (node (ref "PMOD1/2") (pin "7") (pinfunction "7_7") (pintype "passive"))
      (node (ref "R27") (pin "2") (pinfunction "2_2") (pintype "passive"))
    )
    (net (code "84") (name "/P3") (class "Default")
      (node (ref "IC3") (pin "85") (pinfunction "IOR_128_85") (pintype "bidirectional"))
      (node (ref "PMOD1/2") (pin "5") (pinfunction "5_5") (pintype "passive"))
      (node (ref "R25") (pin "2") (pinfunction "2_2") (pintype "passive"))
    )
    (net (code "85") (name "/P4") (class "Default")
      (node (ref "IC3") (pin "95") (pinfunction "IOR_144_95") (pintype "bidirectional"))
      (node (ref "PMOD1/2") (pin "12") (pinfunction "12_12") (pintype "passive"))
    )
    (net (code "86") (name "/P5") (class "Default")
      (node (ref "IC3") (pin "93") (pinfunction "IOR_140_GBIN3_93") (pintype "bidirectional"))
      (node (ref "PMOD1/2") (pin "10") (pinfunction "10_10") (pintype "passive"))
    )
    (net (code "87") (name "/P6") (class "Default")
      (node (ref "IC3") (pin "90") (pinfunction "IOR_138_90") (pintype "bidirectional"))
      (node (ref "PMOD1/2") (pin "8") (pinfunction "8_8") (pintype "passive"))
    )
    (net (code "88") (name "/P7") (class "Default")
      (node (ref "IC3") (pin "87") (pinfunction "IOR_136_87") (pintype "bidirectional"))
      (node (ref "PMOD1/2") (pin "6") (pinfunction "6_6") (pintype "passive"))
    )
    (net (code "89") (name "/P8") (class "Default")
      (node (ref "IC3") (pin "105") (pinfunction "IOR_165_105") (pintype "bidirectional"))
      (node (ref "PMOD3/4") (pin "11") (pinfunction "11_11") (pintype "passive"))
    )
    (net (code "90") (name "/P9") (class "Default")
      (node (ref "IC3") (pin "102") (pinfunction "IOR_161_102") (pintype "bidirectional"))
      (node (ref "PMOD3/4") (pin "9") (pinfunction "9_9") (pintype "passive"))
    )
    (net (code "91") (name "/P10") (class "Default")
      (node (ref "IC3") (pin "99") (pinfunction "IOR_152_99") (pintype "bidirectional"))
      (node (ref "PMOD3/4") (pin "7") (pinfunction "7_7") (pintype "passive"))
    )
    (net (code "92") (name "/P11") (class "Default")
      (node (ref "IC3") (pin "97") (pinfunction "IOR_147_97") (pintype "bidirectional"))
      (node (ref "PMOD3/4") (pin "5") (pinfunction "5_5") (pintype "passive"))
    )
    (net (code "93") (name "/P12") (class "Default")
      (node (ref "IC3") (pin "104") (pinfunction "IOR_164_104") (pintype "bidirectional"))
      (node (ref "PMOD3/4") (pin "12") (pinfunction "12_12") (pintype "passive"))
    )
    (net (code "94") (name "/P13") (class "Default")
      (node (ref "IC3") (pin "101") (pinfunction "IOR_160_101") (pintype "bidirectional"))
      (node (ref "PMOD3/4") (pin "10") (pinfunction "10_10") (pintype "passive"))
    )
    (net (code "95") (name "/P14") (class "Default")
      (node (ref "IC3") (pin "98") (pinfunction "IOR_148_98") (pintype "bidirectional"))
      (node (ref "PMOD3/4") (pin "8") (pinfunction "8_8") (pintype "passive"))
    )
    (net (code "96") (name "/P15") (class "Default")
      (node (ref "IC3") (pin "96") (pinfunction "IOR_146_96") (pintype "bidirectional"))
      (node (ref "PMOD3/4") (pin "6") (pinfunction "6_6") (pintype "passive"))
    )
    (net (code "97") (name "/P16") (class "Default")
      (node (ref "IC3") (pin "143") (pinfunction "IOT_221_143") (pintype "bidirectional"))
      (node (ref "PMOD5/6") (pin "11") (pinfunction "11_11") (pintype "passive"))
    )
    (net (code "98") (name "/P17") (class "Default")
      (node (ref "IC3") (pin "114") (pinfunction "IOT_171_114") (pintype "bidirectional"))
      (node (ref "PMOD5/6") (pin "9") (pinfunction "9_9") (pintype "passive"))
    )
    (net (code "99") (name "/P18") (class "Default")
      (node (ref "IC3") (pin "112") (pinfunction "IOT_169_112") (pintype "bidirectional"))
      (node (ref "PMOD5/6") (pin "7") (pinfunction "7_7") (pintype "passive"))
    )
    (net (code "100") (name "/P19") (class "Default")
      (node (ref "IC3") (pin "107") (pinfunction "IOR_167_107") (pintype "bidirectional"))
      (node (ref "PMOD5/6") (pin "5") (pinfunction "5_5") (pintype "passive"))
    )
    (net (code "101") (name "/P20") (class "Default")
      (node (ref "IC3") (pin "144") (pinfunction "IOT_222_144") (pintype "bidirectional"))
      (node (ref "PMOD5/6") (pin "12") (pinfunction "12_12") (pintype "passive"))
    )
    (net (code "102") (name "/P21") (class "Default")
      (node (ref "IC3") (pin "113") (pinfunction "IOT_170_113") (pintype "bidirectional"))
      (node (ref "PMOD5/6") (pin "10") (pinfunction "10_10") (pintype "passive"))
    )
    (net (code "103") (name "/P22") (class "Default")
      (node (ref "IC3") (pin "110") (pinfunction "IOT_168_110") (pintype "bidirectional"))
      (node (ref "PMOD5/6") (pin "8") (pinfunction "8_8") (pintype "passive"))
    )
    (net (code "104") (name "/P23") (class "Default")
      (node (ref "IC3") (pin "106") (pinfunction "IOR_166_106") (pintype "bidirectional"))
      (node (ref "PMOD5/6") (pin "6") (pinfunction "6_6") (pintype "passive"))
    )
    (net (code "105") (name "/P24") (class "Default")
      (node (ref "IC3") (pin "10") (pinfunction "IOL_5B_10") (pintype "bidirectional"))
      (node (ref "OLI-EXP") (pin "15") (pinfunction "KL_15") (pintype "passive"))
      (node (ref "PMOD7/8") (pin "11") (pinfunction "11_11") (pintype "passive"))
    )
    (net (code "106") (name "/P25") (class "Default")
      (node (ref "IC3") (pin "9") (pinfunction "IOL_5A_9") (pintype "bidirectional"))
      (node (ref "OLI-EXP") (pin "13") (pinfunction "KL_13") (pintype "passive"))
      (node (ref "PMOD7/8") (pin "9") (pinfunction "9_9") (pintype "passive"))
    )
    (net (code "107") (name "/P26") (class "Default")
      (node (ref "IC3") (pin "2") (pinfunction "IOL_2B_2") (pintype "bidirectional"))
      (node (ref "OLI-EXP") (pin "7") (pinfunction "KL_7") (pintype "passive"))
      (node (ref "PMOD7/8") (pin "7") (pinfunction "7_7") (pintype "passive"))
    )
    (net (code "108") (name "/P27") (class "Default")
      (node (ref "IC3") (pin "1") (pinfunction "IOL_2A_1") (pintype "bidirectional"))
      (node (ref "OLI-EXP") (pin "5") (pinfunction "KL_5") (pintype "passive"))
      (node (ref "PMOD7/8") (pin "5") (pinfunction "5_5") (pintype "passive"))
    )
    (net (code "109") (name "/P28") (class "Default")
      (node (ref "IC3") (pin "8") (pinfunction "IOL_4B_8") (pintype "bidirectional"))
      (node (ref "OLI-EXP") (pin "12") (pinfunction "KL_12") (pintype "passive"))
      (node (ref "PMOD7/8") (pin "12") (pinfunction "12_12") (pintype "passive"))
    )
    (net (code "110") (name "/P29") (class "Default")
      (node (ref "IC3") (pin "7") (pinfunction "IOL_4A_7") (pintype "bidirectional"))
      (node (ref "OLI-EXP") (pin "10") (pinfunction "KL_10") (pintype "passive"))
      (node (ref "PMOD7/8") (pin "10") (pinfunction "10_10") (pintype "passive"))
    )
    (net (code "111") (name "/P30") (class "Default")
      (node (ref "IC3") (pin "4") (pinfunction "IOL_3B_4") (pintype "bidirectional"))
      (node (ref "OLI-EXP") (pin "11") (pinfunction "KL_11") (pintype "passive"))
      (node (ref "PMOD7/8") (pin "8") (pinfunction "8_8") (pintype "passive"))
    )
    (net (code "112") (name "/P31") (class "Default")
      (node (ref "IC3") (pin "3") (pinfunction "IOL_3A_3") (pintype "bidirectional"))
      (node (ref "OLI-EXP") (pin "9") (pinfunction "KL_9") (pintype "passive"))
      (node (ref "PMOD7/8") (pin "6") (pinfunction "6_6") (pintype "passive"))
    )
    (net (code "113") (name "/P32") (class "Default")
      (node (ref "IC3") (pin "20") (pinfunction "IOL_13B_GBIN7_20") (pintype "bidirectional"))
      (node (ref "OLI-EXP") (pin "23") (pinfunction "KL_23") (pintype "passive"))
      (node (ref "PMOD9/10") (pin "11") (pinfunction "11_11") (pintype "passive"))
    )
    (net (code "114") (name "/P33") (class "Default")
      (node (ref "IC3") (pin "19") (pinfunction "IOL_13A_19") (pintype "bidirectional"))
      (node (ref "OLI-EXP") (pin "21") (pinfunction "KL_21") (pintype "passive"))
      (node (ref "PMOD9/10") (pin "9") (pinfunction "9_9") (pintype "passive"))
    )
    (net (code "115") (name "/P34") (class "Default")
      (node (ref "IC3") (pin "16") (pinfunction "IOL_10B_16") (pintype "bidirectional"))
      (node (ref "OLI-EXP") (pin "19") (pinfunction "KL_19") (pintype "passive"))
      (node (ref "PMOD9/10") (pin "7") (pinfunction "7_7") (pintype "passive"))
    )
    (net (code "116") (name "/P35") (class "Default")
      (node (ref "IC3") (pin "15") (pinfunction "IOL_10A_15") (pintype "bidirectional"))
      (node (ref "OLI-EXP") (pin "17") (pinfunction "KL_17") (pintype "passive"))
      (node (ref "PMOD9/10") (pin "5") (pinfunction "5_5") (pintype "passive"))
    )
    (net (code "117") (name "/P36") (class "Default")
      (node (ref "IC3") (pin "18") (pinfunction "IOL_12B_18") (pintype "bidirectional"))
      (node (ref "OLI-EXP") (pin "20") (pinfunction "KL_20") (pintype "passive"))
      (node (ref "PMOD9/10") (pin "12") (pinfunction "12_12") (pintype "passive"))
    )
    (net (code "118") (name "/P37") (class "Default")
      (node (ref "IC3") (pin "17") (pinfunction "IOL_12A_17") (pintype "bidirectional"))
      (node (ref "OLI-EXP") (pin "18") (pinfunction "KL_18") (pintype "passive"))
      (node (ref "PMOD9/10") (pin "10") (pinfunction "10_10") (pintype "passive"))
    )
    (net (code "119") (name "/P38") (class "Default")
      (node (ref "IC3") (pin "12") (pinfunction "IOL_8B_12") (pintype "bidirectional"))
      (node (ref "OLI-EXP") (pin "16") (pinfunction "KL_16") (pintype "passive"))
      (node (ref "PMOD9/10") (pin "8") (pinfunction "8_8") (pintype "passive"))
    )
    (net (code "120") (name "/P39") (class "Default")
      (node (ref "IC3") (pin "11") (pinfunction "IOL_8A_11") (pintype "bidirectional"))
      (node (ref "OLI-EXP") (pin "14") (pinfunction "KL_14") (pintype "passive"))
      (node (ref "PMOD9/10") (pin "6") (pinfunction "6_6") (pintype "passive"))
    )
    (net (code "121") (name "/P40") (class "Default")
      (node (ref "IC3") (pin "34") (pinfunction "IOL_25B_34") (pintype "bidirectional"))
      (node (ref "OLI-EXP") (pin "34") (pinfunction "KL_34") (pintype "passive"))
      (node (ref "PMOD11/12") (pin "11") (pinfunction "11_11") (pintype "passive"))
    )
    (net (code "122") (name "/P41") (class "Default")
      (node (ref "IC3") (pin "33") (pinfunction "IOL_25A_33") (pintype "bidirectional"))
      (node (ref "OLI-EXP") (pin "32") (pinfunction "KL_32") (pintype "passive"))
      (node (ref "PMOD11/12") (pin "9") (pinfunction "9_9") (pintype "passive"))
    )
    (net (code "123") (name "/P42") (class "Default")
      (node (ref "IC3") (pin "22") (pinfunction "IOL_14B_22") (pintype "bidirectional"))
      (node (ref "OLI-EXP") (pin "25") (pinfunction "KL_25") (pintype "passive"))
      (node (ref "PMOD11/12") (pin "7") (pinfunction "7_7") (pintype "passive"))
    )
    (net (code "124") (name "/P43") (class "Default")
      (node (ref "IC3") (pin "21") (pinfunction "IOL_14A_GBIN6_21") (pintype "bidirectional"))
      (node (ref "OLI-EXP") (pin "22") (pinfunction "KL_22") (pintype "passive"))
      (node (ref "PMOD11/12") (pin "5") (pinfunction "5_5") (pintype "passive"))
    )
    (net (code "125") (name "/P44") (class "Default")
      (node (ref "IC3") (pin "32") (pinfunction "IOL_24B_32") (pintype "bidirectional"))
      (node (ref "OLI-EXP") (pin "30") (pinfunction "KL_30") (pintype "passive"))
      (node (ref "PMOD11/12") (pin "12") (pinfunction "12_12") (pintype "passive"))
    )
    (net (code "126") (name "/P45") (class "Default")
      (node (ref "IC3") (pin "31") (pinfunction "IOL_24A_31") (pintype "bidirectional"))
      (node (ref "OLI-EXP") (pin "28") (pinfunction "KL_28") (pintype "passive"))
      (node (ref "PMOD11/12") (pin "10") (pinfunction "10_10") (pintype "passive"))
    )
    (net (code "127") (name "/P46") (class "Default")
      (node (ref "IC3") (pin "26") (pinfunction "IOL_18B_26") (pintype "bidirectional"))
      (node (ref "OLI-EXP") (pin "26") (pinfunction "KL_26") (pintype "passive"))
      (node (ref "PMOD11/12") (pin "8") (pinfunction "8_8") (pintype "passive"))
    )
    (net (code "128") (name "/P47") (class "Default")
      (node (ref "IC3") (pin "25") (pinfunction "IOL_18_A_25") (pintype "bidirectional"))
      (node (ref "OLI-EXP") (pin "24") (pinfunction "KL_24") (pintype "passive"))
      (node (ref "PMOD11/12") (pin "6") (pinfunction "6_6") (pintype "passive"))
    )
    (net (code "129") (name "/P52") (class "Default")
      (node (ref "IC6") (pin "14") (pinfunction "4B1_14") (pintype "bidirectional"))
      (node (ref "PMOD14") (pin "1") (pinfunction "1_1") (pintype "passive"))
      (node (ref "R1") (pin "2") (pinfunction "2_2") (pintype "passive"))
    )
    (net (code "130") (name "/P53") (class "Default")
      (node (ref "IC6") (pin "11") (pinfunction "3B1_11") (pintype "bidirectional"))
      (node (ref "PMOD14") (pin "2") (pinfunction "2_2") (pintype "passive"))
      (node (ref "R3") (pin "2") (pinfunction "2_2") (pintype "passive"))
    )
    (net (code "131") (name "/P54") (class "Default")
      (node (ref "IC6") (pin "5") (pinfunction "2B1_5") (pintype "bidirectional"))
      (node (ref "PMOD14") (pin "3") (pinfunction "3_3") (pintype "passive"))
      (node (ref "R2") (pin "2") (pinfunction "2_2") (pintype "passive"))
    )
    (net (code "132") (name "/P55") (class "Default")
      (node (ref "IC6") (pin "2") (pinfunction "1B1_2") (pintype "bidirectional"))
      (node (ref "PMOD14") (pin "4") (pinfunction "4_4") (pintype "passive"))
      (node (ref "R4") (pin "2") (pinfunction "2_2") (pintype "passive"))
    )
    (net (code "133") (name "/QCK") (class "Default")
      (node (ref "IC3") (pin "82") (pinfunction "IOR_118_82") (pintype "bidirectional"))
      (node (ref "IC4") (pin "17") (pinfunction "PA3_17") (pintype "bidirectional"))
    )
    (net (code "134") (name "/QD0") (class "Default")
      (node (ref "IC3") (pin "83") (pinfunction "IOR_119_83") (pintype "bidirectional"))
      (node (ref "IC4") (pin "27") (pinfunction "PB1_27") (pintype "bidirectional"))
    )
    (net (code "135") (name "/QD1") (class "Default")
      (node (ref "IC3") (pin "84") (pinfunction "IOR_120_84") (pintype "bidirectional"))
      (node (ref "IC4") (pin "26") (pinfunction "PB0_26") (pintype "bidirectional"))
    )
    (net (code "136") (name "/QD2") (class "Default")
      (node (ref "IC3") (pin "79") (pinfunction "IOR_115_79") (pintype "bidirectional"))
      (node (ref "IC4") (pin "23") (pinfunction "PA7_23") (pintype "power_in"))
    )
    (net (code "137") (name "/QD3") (class "Default")
      (node (ref "IC3") (pin "80") (pinfunction "IOR_116_80") (pintype "bidirectional"))
      (node (ref "IC4") (pin "22") (pinfunction "PA6_22") (pintype "bidirectional"))
    )
    (net (code "138") (name "/RAM_CS") (class "Default")
      (node (ref "IC2") (pin "6") (pinfunction "~{CS1}_6") (pintype "input"))
      (node (ref "IC3") (pin "23") (pinfunction "IOL_17A_23") (pintype "bidirectional"))
      (node (ref "OLI-EXP") (pin "27") (pinfunction "KL_27") (pintype "passive"))
      (node (ref "R30") (pin "1") (pinfunction "1_1") (pintype "passive"))
    )
    (net (code "139") (name "/RAM_LB") (class "Default")
      (node (ref "IC2") (pin "39") (pinfunction "~{LB}_39") (pintype "passive"))
      (node (ref "IC3") (pin "24") (pinfunction "IOL_17B_24") (pintype "bidirectional"))
      (node (ref "OLI-EXP") (pin "29") (pinfunction "KL_29") (pintype "passive"))
    )
    (net (code "140") (name "/RAM_OE") (class "Default")
      (node (ref "IC2") (pin "41") (pinfunction "~{OE}_41") (pintype "input"))
      (node (ref "IC3") (pin "29") (pinfunction "IOL_23B_29") (pintype "bidirectional"))
      (node (ref "OLI-EXP") (pin "33") (pinfunction "KL_33") (pintype "passive"))
    )
    (net (code "141") (name "/RAM_UB") (class "Default")
      (node (ref "IC2") (pin "40") (pinfunction "~{UB}_40") (pintype "passive"))
      (node (ref "IC3") (pin "28") (pinfunction "IOL_23A_28") (pintype "bidirectional"))
      (node (ref "OLI-EXP") (pin "31") (pinfunction "KL_31") (pintype "passive"))
    )
    (net (code "142") (name "/RAM_WE") (class "Default")
      (node (ref "IC2") (pin "17") (pinfunction "~{WE}_17") (pintype "input"))
      (node (ref "IC3") (pin "120") (pinfunction "IOT_179_120") (pintype "bidirectional"))
    )
    (net (code "143") (name "/RESET") (class "Default")
      (node (ref "COMS") (pin "18") (pinfunction "18_18") (pintype "passive"))
      (node (ref "IC3") (pin "66") (pinfunction "CRESET_B_66") (pintype "bidirectional"))
      (node (ref "IC4") (pin "58") (pinfunction "PB6_58") (pintype "bidirectional"))
    )
    (net (code "144") (name "/RX") (class "Default")
      (node (ref "COMS") (pin "8") (pinfunction "8_8") (pintype "passive"))
      (node (ref "IC1") (pin "2") (pinfunction "TX_2") (pintype "bidirectional"))
      (node (ref "IC4") (pin "43") (pinfunction "PA10_43") (pintype "bidirectional"))
      (node (ref "R27") (pin "1") (pinfunction "1_1") (pintype "passive"))
    )
    (net (code "145") (name "/S") (class "Default")
      (node (ref "COMS") (pin "12") (pinfunction "12_12") (pintype "passive"))
      (node (ref "IC4") (pin "3") (pinfunction "PC14-OSC32_IN_3") (pintype "input"))
      (node (ref "IC6") (pin "1") (pinfunction "B2/~{B1}_1") (pintype "bidirectional"))
    )
    (net (code "146") (name "/SCK") (class "Default")
      (node (ref "IC3") (pin "70") (pinfunction "IOB_107_SCK_70") (pintype "bidirectional"))
      (node (ref "IC4") (pin "55") (pinfunction "PB3_55") (pintype "bidirectional"))
      (node (ref "IC6") (pin "4") (pinfunction "1A_4") (pintype "bidirectional"))
    )
    (net (code "147") (name "/SCL") (class "Default")
      (node (ref "COMS") (pin "5") (pinfunction "5_5") (pintype "passive"))
      (node (ref "DIGITAL2") (pin "10") (pinfunction "10_10") (pintype "passive"))
      (node (ref "IC4") (pin "61") (pinfunction "PB8_61") (pintype "bidirectional"))
    )
    (net (code "148") (name "/SDA") (class "Default")
      (node (ref "COMS") (pin "3") (pinfunction "3_3") (pintype "passive"))
      (node (ref "DIGITAL2") (pin "9") (pinfunction "9_9") (pintype "passive"))
      (node (ref "IC4") (pin "62") (pinfunction "PB9_62") (pintype "bidirectional"))
    )
    (net (code "149") (name "/SWCLK") (class "Default")
      (node (ref "COMS") (pin "7") (pinfunction "7_7") (pintype "passive"))
      (node (ref "IC4") (pin "49") (pinfunction "PA14_49") (pintype "bidirectional"))
      (node (ref "R13") (pin "2") (pinfunction "2_2") (pintype "passive"))
    )
    (net (code "150") (name "/SWDIO") (class "Default")
      (node (ref "COMS") (pin "11") (pinfunction "11_11") (pintype "passive"))
      (node (ref "IC4") (pin "46") (pinfunction "PA13_46") (pintype "bidirectional"))
      (node (ref "R11") (pin "2") (pinfunction "2_2") (pintype "passive"))
    )
    (net (code "151") (name "/TX") (class "Default")
      (node (ref "COMS") (pin "10") (pinfunction "10_10") (pintype "passive"))
      (node (ref "IC1") (pin "3") (pinfunction "RX_3") (pintype "bidirectional"))
      (node (ref "IC4") (pin "42") (pinfunction "PA9_42") (pintype "bidirectional"))
      (node (ref "R25") (pin "1") (pinfunction "1_1") (pintype "passive"))
    )
    (net (code "152") (name "/VBAT") (class "Default")
      (node (ref "C33") (pin "2") (pinfunction "2_2") (pintype "passive"))
      (node (ref "IC4") (pin "1") (pinfunction "VBAT_1") (pintype "input"))
    )
    (net (code "153") (name "/VBUS") (class "Default")
      (node (ref "COM") (pin "P$1") (pinfunction "VBUS_P$1") (pintype "bidirectional"))
      (node (ref "D1") (pin "A") (pinfunction "A_A") (pintype "passive"))
      (node (ref "U$2") (pin "P$1") (pinfunction "VBUS_P$1") (pintype "bidirectional"))
    )
    (net (code "154") (name "/VDD_ADC") (class "Default")
      (node (ref "C28") (pin "2") (pinfunction "2_2") (pintype "passive"))
      (node (ref "IC4") (pin "13") (pinfunction "VDDA_13") (pintype "power_in"))
      (node (ref "L3") (pin "2") (pinfunction "2_2") (pintype "passive"))
    )
    (net (code "155") (name "/~{ESS}") (class "Default")
      (node (ref "COMS") (pin "24") (pinfunction "24_24") (pintype "passive"))
      (node (ref "IC6") (pin "13") (pinfunction "4B2_13") (pintype "bidirectional"))
    )
    (net (code "156") (name "/~{QCS}") (class "Default")
      (node (ref "IC3") (pin "81") (pinfunction "IOR_117_81") (pintype "bidirectional"))
      (node (ref "IC4") (pin "16") (pinfunction "PA2_16") (pintype "bidirectional"))
    )
    (net (code "157") (name "/~{RESET}") (class "Default")
      (node (ref "C1") (pin "1") (pinfunction "1_1") (pintype "passive"))
      (node (ref "COMS") (pin "13") (pinfunction "13_13") (pintype "passive"))
      (node (ref "DIGITAL3") (pin "7") (pinfunction "7_7") (pintype "passive"))
      (node (ref "IC4") (pin "7") (pinfunction "NRST_7") (pintype "output"))
      (node (ref "R23") (pin "1") (pinfunction "1_1") (pintype "passive"))
      (node (ref "S0") (pin "2") (pinfunction "2_2") (pintype "passive"))
    )
    (net (code "158") (name "/~{SS}") (class "Default")
      (node (ref "IC3") (pin "71") (pinfunction "IOB_108_SS_71") (pintype "bidirectional"))
      (node (ref "IC4") (pin "50") (pinfunction "PA15_50") (pintype "bidirectional"))
      (node (ref "IC6") (pin "12") (pinfunction "4A_12") (pintype "bidirectional"))
      (node (ref "R35") (pin "2") (pinfunction "2_2") (pintype "passive"))
    )
    (net (code "159") (name "5V") (class "Default")
      (node (ref "5V") (pin "TP") (pinfunction "TP_TP") (pintype "input"))
      (node (ref "C16") (pin "1") (pinfunction "1_1") (pintype "passive"))
      (node (ref "C17") (pin "1") (pinfunction "1_1") (pintype "passive"))
      (node (ref "C20") (pin "1") (pinfunction "1_1") (pintype "passive"))
      (node (ref "C53") (pin "1") (pinfunction "1_1") (pintype "passive"))
      (node (ref "C60") (pin "1") (pinfunction "1_1") (pintype "passive"))
      (node (ref "DIGITAL3") (pin "12") (pinfunction "12_12") (pintype "passive"))
      (node (ref "DIGITAL3") (pin "9") (pinfunction "9_9") (pintype "passive"))
      (node (ref "F1") (pin "2") (pinfunction "2_2") (pintype "passive"))
      (node (ref "IC8") (pin "3") (pinfunction "VIN_3") (pintype "input"))
      (node (ref "OLI-EXP") (pin "1") (pinfunction "KL_1") (pintype "passive"))
    )
    (net (code "160") (name "GND") (class "Default")
      (node (ref "C1") (pin "2") (pinfunction "2_2") (pintype "passive"))
      (node (ref "C10") (pin "1") (pinfunction "1_1") (pintype "passive"))
      (node (ref "C11") (pin "2") (pinfunction "2_2") (pintype "passive"))
      (node (ref "C12") (pin "2") (pinfunction "2_2") (pintype "passive"))
      (node (ref "C13") (pin "2") (pinfunction "2_2") (pintype "passive"))
      (node (ref "C14") (pin "2") (pinfunction "2_2") (pintype "passive"))
      (node (ref "C16") (pin "2") (pinfunction "2_2") (pintype "passive"))
      (node (ref "C17") (pin "2") (pinfunction "2_2") (pintype "passive"))
      (node (ref "C18") (pin "2") (pinfunction "2_2") (pintype "passive"))
      (node (ref "C19") (pin "2") (pinfunction "2_2") (pintype "passive"))
      (node (ref "C2") (pin "2") (pinfunction "2_2") (pintype "passive"))
      (node (ref "C20") (pin "2") (pinfunction "2_2") (pintype "passive"))
      (node (ref "C23") (pin "2") (pinfunction "2_2") (pintype "passive"))
      (node (ref "C24") (pin "1") (pinfunction "1_1") (pintype "passive"))
      (node (ref "C25") (pin "1") (pinfunction "1_1") (pintype "passive"))
      (node (ref "C26") (pin "1") (pinfunction "1_1") (pintype "passive"))
      (node (ref "C27") (pin "1") (pinfunction "1_1") (pintype "passive"))
      (node (ref "C28") (pin "1") (pinfunction "1_1") (pintype "passive"))
      (node (ref "C29") (pin "1") (pinfunction "1_1") (pintype "passive"))
      (node (ref "C3") (pin "2") (pinfunction "2_2") (pintype "passive"))
      (node (ref "C30") (pin "1") (pinfunction "1_1") (pintype "passive"))
      (node (ref "C31") (pin "1") (pinfunction "1_1") (pintype "passive"))
      (node (ref "C32") (pin "1") (pinfunction "1_1") (pintype "passive"))
      (node (ref "C33") (pin "1") (pinfunction "1_1") (pintype "passive"))
      (node (ref "C34") (pin "1") (pinfunction "1_1") (pintype "passive"))
      (node (ref "C35") (pin "2") (pinfunction "2_2") (pintype "passive"))
      (node (ref "C37") (pin "2") (pinfunction "2_2") (pintype "passive"))
      (node (ref "C38") (pin "2") (pinfunction "2_2") (pintype "passive"))
      (node (ref "C39") (pin "1") (pinfunction "1_1") (pintype "passive"))
      (node (ref "C4") (pin "2") (pinfunction "2_2") (pintype "passive"))
      (node (ref "C40") (pin "1") (pinfunction "1_1") (pintype "passive"))
      (node (ref "C41") (pin "1") (pinfunction "1_1") (pintype "passive"))
      (node (ref "C42") (pin "2") (pinfunction "2_2") (pintype "passive"))
      (node (ref "C43") (pin "2") (pinfunction "2_2") (pintype "passive"))
      (node (ref "C44") (pin "2") (pinfunction "2_2") (pintype "passive"))
      (node (ref "C45") (pin "2") (pinfunction "2_2") (pintype "passive"))
      (node (ref "C46") (pin "2") (pinfunction "2_2") (pintype "passive"))
      (node (ref "C47") (pin "2") (pinfunction "2_2") (pintype "passive"))
      (node (ref "C48") (pin "2") (pinfunction "2_2") (pintype "passive"))
      (node (ref "C49") (pin "2") (pinfunction "2_2") (pintype "passive"))
      (node (ref "C5") (pin "2") (pinfunction "2_2") (pintype "passive"))
      (node (ref "C50") (pin "2") (pinfunction "2_2") (pintype "passive"))
      (node (ref "C51") (pin "2") (pinfunction "2_2") (pintype "passive"))
      (node (ref "C52") (pin "2") (pinfunction "2_2") (pintype "passive"))
      (node (ref "C53") (pin "2") (pinfunction "2_2") (pintype "passive"))
      (node (ref "C54") (pin "2") (pinfunction "2_2") (pintype "passive"))
      (node (ref "C55") (pin "2") (pinfunction "2_2") (pintype "passive"))
      (node (ref "C56") (pin "2") (pinfunction "2_2") (pintype "passive"))
      (node (ref "C57") (pin "2") (pinfunction "2_2") (pintype "passive"))
      (node (ref "C58") (pin "1") (pinfunction "1_1") (pintype "passive"))
      (node (ref "C59") (pin "2") (pinfunction "2_2") (pintype "passive"))
      (node (ref "C6") (pin "1") (pinfunction "1_1") (pintype "passive"))
      (node (ref "C60") (pin "2") (pinfunction "2_2") (pintype "passive"))
      (node (ref "C61") (pin "-") (pinfunction "-_-") (pintype "passive"))
      (node (ref "C62") (pin "1") (pinfunction "1_1") (pintype "passive"))
      (node (ref "C63") (pin "1") (pinfunction "1_1") (pintype "passive"))
      (node (ref "C7") (pin "2") (pinfunction "2_2") (pintype "passive"))
      (node (ref "C8") (pin "2") (pinfunction "2_2") (pintype "passive"))
      (node (ref "COM") (pin "P$5") (pinfunction "GND_P$5") (pintype "bidirectional"))
      (node (ref "COMS") (pin "14") (pinfunction "14_14") (pintype "passive"))
      (node (ref "COMS") (pin "20") (pinfunction "20_20") (pintype "passive"))
      (node (ref "COMS") (pin "25") (pinfunction "25_25") (pintype "passive"))
      (node (ref "COMS") (pin "6") (pinfunction "6_6") (pintype "passive"))
      (node (ref "COMS") (pin "9") (pinfunction "9_9") (pintype "passive"))
      (node (ref "DIGITAL2") (pin "7") (pinfunction "7_7") (pintype "passive"))
      (node (ref "DIGITAL3") (pin "10") (pinfunction "10_10") (pintype "passive"))
      (node (ref "DIGITAL3") (pin "11") (pinfunction "11_11") (pintype "passive"))
      (node (ref "ESD1") (pin "1") (pinfunction "GND_1") (pintype "bidirectional"))
      (node (ref "IC1") (pin "1") (pinfunction "GND_1") (pintype "bidirectional"))
      (node (ref "IC2") (pin "12") (pinfunction "GND_2_12") (pintype "passive"))
      (node (ref "IC2") (pin "34") (pinfunction "GND_34") (pintype "passive"))
      (node (ref "IC3") (pin "103") (pinfunction "GND_103") (pintype "bidirectional"))
      (node (ref "IC3") (pin "13") (pinfunction "GND_13") (pintype "bidirectional"))
      (node (ref "IC3") (pin "132") (pinfunction "GND_132") (pintype "bidirectional"))
      (node (ref "IC3") (pin "14") (pinfunction "GND_14") (pintype "bidirectional"))
      (node (ref "IC3") (pin "140") (pinfunction "GND_140") (pintype "bidirectional"))
      (node (ref "IC3") (pin "5") (pinfunction "GND_5") (pintype "bidirectional"))
      (node (ref "IC3") (pin "59") (pinfunction "GND_59") (pintype "bidirectional"))
      (node (ref "IC3") (pin "69") (pinfunction "GND_69") (pintype "bidirectional"))
      (node (ref "IC3") (pin "86") (pinfunction "GND_86") (pintype "bidirectional"))
      (node (ref "IC4") (pin "12") (pinfunction "VSSA_12") (pintype "passive"))
      (node (ref "IC4") (pin "18") (pinfunction "VSS_4_18") (pintype "passive"))
      (node (ref "IC4") (pin "31") (pinfunction "VSS_1_31") (pintype "passive"))
      (node (ref "IC4") (pin "47") (pinfunction "VSS_2_47") (pintype "passive"))
      (node (ref "IC4") (pin "63") (pinfunction "VSS_3_63") (pintype "passive"))
      (node (ref "IC6") (pin "8") (pinfunction "GND_8") (pintype "power_in"))
      (node (ref "IC7") (pin "2") (pinfunction "GND_2") (pintype "power_in"))
      (node (ref "IC8") (pin "1") (pinfunction "GND_1") (pintype "power_in"))
      (node (ref "LED1") (pin "C") (pinfunction "C_C") (pintype "passive"))
      (node (ref "LED2") (pin "C") (pinfunction "C_C") (pintype "passive"))
      (node (ref "LED3") (pin "C") (pinfunction "C_C") (pintype "passive"))
      (node (ref "LED4") (pin "C") (pinfunction "C_C") (pintype "passive"))
      (node (ref "OLI-EXP") (pin "2") (pinfunction "KL_2") (pintype "passive"))
      (node (ref "OLI-EXP") (pin "4") (pinfunction "KL_4") (pintype "passive"))
      (node (ref "OLI-EXP") (pin "8") (pinfunction "KL_8") (pintype "passive"))
      (node (ref "PMOD1/2") (pin "3") (pinfunction "3_3") (pintype "passive"))
      (node (ref "PMOD1/2") (pin "4") (pinfunction "4_4") (pintype "passive"))
      (node (ref "PMOD11/12") (pin "3") (pinfunction "3_3") (pintype "passive"))
      (node (ref "PMOD11/12") (pin "4") (pinfunction "4_4") (pintype "passive"))
      (node (ref "PMOD13") (pin "5") (pinfunction "5_5") (pintype "passive"))
      (node (ref "PMOD14") (pin "5") (pinfunction "5_5") (pintype "passive"))
      (node (ref "PMOD3/4") (pin "3") (pinfunction "3_3") (pintype "passive"))
      (node (ref "PMOD3/4") (pin "4") (pinfunction "4_4") (pintype "passive"))
      (node (ref "PMOD5/6") (pin "3") (pinfunction "3_3") (pintype "passive"))
      (node (ref "PMOD5/6") (pin "4") (pinfunction "4_4") (pintype "passive"))
      (node (ref "PMOD7/8") (pin "3") (pinfunction "3_3") (pintype "passive"))
      (node (ref "PMOD7/8") (pin "4") (pinfunction "4_4") (pintype "passive"))
      (node (ref "PMOD9/10") (pin "3") (pinfunction "3_3") (pintype "passive"))
      (node (ref "PMOD9/10") (pin "4") (pinfunction "4_4") (pintype "passive"))
      (node (ref "PWR") (pin "C") (pinfunction "C_C") (pintype "passive"))
      (node (ref "R13") (pin "1") (pinfunction "1_1") (pintype "passive"))
      (node (ref "R14") (pin "2") (pinfunction "2_2") (pintype "passive"))
      (node (ref "R22") (pin "2") (pinfunction "2_2") (pintype "passive"))
      (node (ref "R24") (pin "2") (pinfunction "2_2") (pintype "passive"))
      (node (ref "S0") (pin "1") (pinfunction "1_1") (pintype "passive"))
      (node (ref "S1") (pin "3") (pinfunction "3_3") (pintype "passive"))
      (node (ref "S1") (pin "4") (pinfunction "4_4") (pintype "passive"))
      (node (ref "S2") (pin "3") (pinfunction "3_3") (pintype "passive"))
      (node (ref "S2") (pin "4") (pinfunction "4_4") (pintype "passive"))
      (node (ref "S3") (pin "1") (pinfunction "1_1") (pintype "passive"))
      (node (ref "S4") (pin "1") (pinfunction "1_1") (pintype "passive"))
      (node (ref "SD1") (pin "6") (pinfunction "VSS_6") (pintype "power_in"))
      (node (ref "SD1") (pin "S1") (pinfunction "S1_S1") (pintype "passive"))
      (node (ref "SD1") (pin "S2") (pinfunction "S2_S2") (pintype "passive"))
      (node (ref "SD1") (pin "S3") (pinfunction "S3_S3") (pintype "passive"))
      (node (ref "SD1") (pin "S4") (pinfunction "S4_S4") (pintype "passive"))
      (node (ref "U$16") (pin "P$1") (pinfunction "P_P$1") (pintype "bidirectional"))
      (node (ref "U$2") (pin "P$5") (pinfunction "GND_P$5") (pintype "bidirectional"))
      (node (ref "U$21") (pin "P$1") (pinfunction "P_P$1") (pintype "bidirectional"))
      (node (ref "U$22") (pin "P$1") (pinfunction "P_P$1") (pintype "bidirectional"))
      (node (ref "U$24") (pin "P$1") (pinfunction "P_P$1") (pintype "bidirectional"))
      (node (ref "X1") (pin "P2") (pinfunction "GND_P2") (pintype "power_in"))
      (node (ref "Y1") (pin "2") (pinfunction "GND_2") (pintype "power_in"))
      (node (ref "Y1") (pin "4") (pinfunction "GND_4") (pintype "passive"))
      (node (ref "Y2") (pin "2") (pinfunction "GND_2") (pintype "power_in"))
      (node (ref "Y2") (pin "4") (pinfunction "GND_4") (pintype "passive"))
    )
    (net (code "161") (name "Net-(COM-D+)") (class "Default")
      (node (ref "COM") (pin "P$3") (pinfunction "D+_P$3") (pintype "bidirectional"))
      (node (ref "IC1") (pin "5") (pinfunction "D+_5") (pintype "bidirectional"))
    )
    (net (code "162") (name "Net-(COM-D-)") (class "Default")
      (node (ref "COM") (pin "P$2") (pinfunction "D-_P$2") (pintype "bidirectional"))
      (node (ref "IC1") (pin "6") (pinfunction "D-_6") (pintype "bidirectional"))
    )
    (net (code "163") (name "Net-(COM-SH3)") (class "Default")
      (node (ref "C26") (pin "2") (pinfunction "2_2") (pintype "passive"))
      (node (ref "COM") (pin "SH5") (pinfunction "SH2_SH5") (pintype "bidirectional"))
      (node (ref "COM") (pin "SH6") (pinfunction "SH4_SH6") (pintype "bidirectional"))
      (node (ref "COM") (pin "SH@2") (pinfunction "SH2_SH@2") (pintype "bidirectional"))
      (node (ref "COM") (pin "SH@3") (pinfunction "SH3_SH@3") (pintype "bidirectional"))
      (node (ref "COM") (pin "SH@4") (pinfunction "SH4_SH@4") (pintype "bidirectional"))
      (node (ref "R24") (pin "1") (pinfunction "1_1") (pintype "passive"))
    )
    (net (code "164") (name "Net-(D1-PadC)") (class "Default")
      (node (ref "D1") (pin "C") (pinfunction "C_C") (pintype "passive"))
      (node (ref "D3") (pin "C") (pinfunction "C_C") (pintype "passive"))
      (node (ref "F1") (pin "1") (pinfunction "1_1") (pintype "passive"))
    )
    (net (code "165") (name "Net-(IC1-XI)") (class "Default")
      (node (ref "C41") (pin "2") (pinfunction "2_2") (pintype "passive"))
      (node (ref "IC1") (pin "7") (pinfunction "XI_7") (pintype "bidirectional"))
      (node (ref "Y2") (pin "3") (pinfunction "X2_3") (pintype "passive"))
    )
    (net (code "166") (name "Net-(IC1-XO)") (class "Default")
      (node (ref "C40") (pin "2") (pinfunction "2_2") (pintype "passive"))
      (node (ref "IC1") (pin "8") (pinfunction "XO_8") (pintype "bidirectional"))
      (node (ref "Y2") (pin "1") (pinfunction "X1_1") (pintype "passive"))
    )
    (net (code "167") (name "Net-(IC3-GNDPLL0)") (class "Default")
      (node (ref "C36") (pin "1") (pinfunction "1_1") (pintype "passive"))
      (node (ref "IC3") (pin "53") (pinfunction "GNDPLL0_53") (pintype "bidirectional"))
    )
    (net (code "168") (name "Net-(IC3-GNDPLL1)") (class "Default")
      (node (ref "C9") (pin "1") (pinfunction "1_1") (pintype "passive"))
      (node (ref "IC3") (pin "127") (pinfunction "GNDPLL1_127") (pintype "bidirectional"))
    )
    (net (code "169") (name "Net-(IC3-VCCPLL0)") (class "Default")
      (node (ref "C36") (pin "2") (pinfunction "2_2") (pintype "passive"))
      (node (ref "IC3") (pin "54") (pinfunction "VCCPLL0_54") (pintype "bidirectional"))
      (node (ref "R38") (pin "1") (pinfunction "1_1") (pintype "passive"))
    )
    (net (code "170") (name "Net-(IC3-VCCPLL1)") (class "Default")
      (node (ref "C9") (pin "2") (pinfunction "2_2") (pintype "passive"))
      (node (ref "IC3") (pin "126") (pinfunction "VCCPLL1_126") (pintype "bidirectional"))
      (node (ref "R39") (pin "2") (pinfunction "2_2") (pintype "passive"))
    )
    (net (code "171") (name "Net-(IC4-PD0_OSC_IN)") (class "Default")
      (node (ref "C27") (pin "2") (pinfunction "2_2") (pintype "passive"))
      (node (ref "IC4") (pin "5") (pinfunction "PD0_OSC_IN_5") (pintype "input"))
      (node (ref "Y1") (pin "1") (pinfunction "X1_1") (pintype "passive"))
    )
    (net (code "172") (name "Net-(IC4-PD1_OSC_OUT)") (class "Default")
      (node (ref "C34") (pin "2") (pinfunction "2_2") (pintype "passive"))
      (node (ref "IC4") (pin "6") (pinfunction "PD1_OSC_OUT_6") (pintype "output"))
      (node (ref "Y1") (pin "3") (pinfunction "X2_3") (pintype "passive"))
    )
    (net (code "173") (name "Net-(IC7-EN)") (class "Default")
      (node (ref "C62") (pin "2") (pinfunction "2_2") (pintype "passive"))
      (node (ref "IC7") (pin "3") (pinfunction "EN_3") (pintype "input"))
      (node (ref "R28") (pin "2") (pinfunction "2_2") (pintype "passive"))
    )
    (net (code "174") (name "Net-(LED5-PadC)") (class "Default")
      (node (ref "LED5") (pin "C") (pinfunction "C_C") (pintype "passive"))
      (node (ref "R5") (pin "2") (pinfunction "2_2") (pintype "passive"))
    )
    (net (code "175") (name "Net-(LED6-PadC)") (class "Default")
      (node (ref "LED6") (pin "C") (pinfunction "C_C") (pintype "passive"))
      (node (ref "R26") (pin "2") (pinfunction "2_2") (pintype "passive"))
    )
    (net (code "176") (name "Net-(OLI-EXPAE-KL)") (class "Default")
      (node (ref "OLI-EXP") (pin "6") (pinfunction "KL_6") (pintype "passive"))
      (node (ref "R43") (pin "2") (pinfunction "2_2") (pintype "passive"))
    )
    (net (code "177") (name "Net-(PWR-PadA)") (class "Default")
      (node (ref "PWR") (pin "A") (pinfunction "A_A") (pintype "passive"))
      (node (ref "R6") (pin "2") (pinfunction "2_2") (pintype "passive"))
    )
    (net (code "178") (name "Net-(U$2-SH3)") (class "Default")
      (node (ref "C39") (pin "2") (pinfunction "2_2") (pintype "passive"))
      (node (ref "R22") (pin "1") (pinfunction "1_1") (pintype "passive"))
      (node (ref "U$2") (pin "SH5") (pinfunction "SH2_SH5") (pintype "bidirectional"))
      (node (ref "U$2") (pin "SH6") (pinfunction "SH4_SH6") (pintype "bidirectional"))
      (node (ref "U$2") (pin "SH@2") (pinfunction "SH2_SH@2") (pintype "bidirectional"))
      (node (ref "U$2") (pin "SH@3") (pinfunction "SH3_SH@3") (pintype "bidirectional"))
      (node (ref "U$2") (pin "SH@4") (pinfunction "SH4_SH@4") (pintype "bidirectional"))
    )
    (net (code "179") (name "Net-(X1-OUT)") (class "Default")
      (node (ref "R43") (pin "1") (pinfunction "1_1") (pintype "passive"))
      (node (ref "R44") (pin "1") (pinfunction "1_1") (pintype "passive"))
      (node (ref "X1") (pin "P3") (pinfunction "OUT_P3") (pintype "output"))
    )
    (net (code "180") (name "VCC") (class "Default")
      (node (ref "C12") (pin "1") (pinfunction "1_1") (pintype "passive"))
      (node (ref "C14") (pin "1") (pinfunction "1_1") (pintype "passive"))
      (node (ref "C19") (pin "1") (pinfunction "1_1") (pintype "passive"))
      (node (ref "C24") (pin "2") (pinfunction "2_2") (pintype "passive"))
      (node (ref "C35") (pin "1") (pinfunction "1_1") (pintype "passive"))
      (node (ref "C55") (pin "1") (pinfunction "1_1") (pintype "passive"))
      (node (ref "C57") (pin "1") (pinfunction "1_1") (pintype "passive"))
      (node (ref "IC3") (pin "111") (pinfunction "VCC_111") (pintype "bidirectional"))
      (node (ref "IC3") (pin "27") (pinfunction "VCC_27") (pintype "bidirectional"))
      (node (ref "IC3") (pin "40") (pinfunction "VCC_40") (pintype "bidirectional"))
      (node (ref "IC3") (pin "92") (pinfunction "VCC_92") (pintype "bidirectional"))
      (node (ref "IC7") (pin "5") (pinfunction "VOUT_5") (pintype "power_in"))
      (node (ref "R38") (pin "2") (pinfunction "2_2") (pintype "passive"))
      (node (ref "R39") (pin "1") (pinfunction "1_1") (pintype "passive"))
      (node (ref "VCC") (pin "TP") (pinfunction "TP_TP") (pintype "input"))
    )
    (net (code "181") (name "unconnected-(COM-ID-PadP$4)") (class "Default")
      (node (ref "COM") (pin "P$4") (pinfunction "ID_P$4") (pintype "bidirectional"))
    )
    (net (code "182") (name "unconnected-(COM-SH1-PadSH@1)") (class "Default")
      (node (ref "COM") (pin "SH@1") (pinfunction "SH1_SH@1") (pintype "bidirectional"))
    )
    (net (code "183") (name "unconnected-(COMS-Pad1)") (class "Default")
      (node (ref "COMS") (pin "1") (pinfunction "1_1") (pintype "passive"))
    )
    (net (code "184") (name "unconnected-(COMS-Pad17)") (class "Default")
      (node (ref "COMS") (pin "17") (pinfunction "17_17") (pintype "passive"))
    )
    (net (code "185") (name "unconnected-(COMS-Pad26)") (class "Default")
      (node (ref "COMS") (pin "26") (pinfunction "26_26") (pintype "passive"))
    )
    (net (code "186") (name "unconnected-(DIGITAL2-Pad8)") (class "Default")
      (node (ref "DIGITAL2") (pin "8") (pinfunction "8_8") (pintype "passive"))
    )
    (net (code "187") (name "unconnected-(IC1-DCD-Pad12)") (class "Default")
      (node (ref "IC1") (pin "12") (pinfunction "DCD_12") (pintype "bidirectional"))
    )
    (net (code "188") (name "unconnected-(IC1-DSR-Pad10)") (class "Default")
      (node (ref "IC1") (pin "10") (pinfunction "DSR_10") (pintype "bidirectional"))
    )
    (net (code "189") (name "unconnected-(IC1-DTR-Pad13)") (class "Default")
      (node (ref "IC1") (pin "13") (pinfunction "DTR_13") (pintype "bidirectional"))
    )
    (net (code "190") (name "unconnected-(IC1-RI-Pad11)") (class "Default")
      (node (ref "IC1") (pin "11") (pinfunction "RI_11") (pintype "bidirectional"))
    )
    (net (code "191") (name "unconnected-(IC1-RS232-Pad15)") (class "Default")
      (node (ref "IC1") (pin "15") (pinfunction "RS232_15") (pintype "bidirectional"))
    )
    (net (code "192") (name "unconnected-(IC2-NC-Pad28)") (class "Default")
      (node (ref "IC2") (pin "28") (pinfunction "NC_28") (pintype "no_connect"))
    )
    (net (code "193") (name "unconnected-(IC3-NC-Pad35)") (class "Default")
      (node (ref "IC3") (pin "35") (pinfunction "NC_35") (pintype "bidirectional"))
    )
    (net (code "194") (name "unconnected-(IC3-NC-Pad36)") (class "Default")
      (node (ref "IC3") (pin "36") (pinfunction "NC_36") (pintype "bidirectional"))
    )
    (net (code "195") (name "unconnected-(IC3-NC-Pad50)") (class "Default")
      (node (ref "IC3") (pin "50") (pinfunction "NC_50") (pintype "bidirectional"))
    )
    (net (code "196") (name "unconnected-(IC3-NC-Pad51)") (class "Default")
      (node (ref "IC3") (pin "51") (pinfunction "NC_51") (pintype "bidirectional"))
    )
    (net (code "197") (name "unconnected-(IC3-NC-Pad58)") (class "Default")
      (node (ref "IC3") (pin "58") (pinfunction "NC_58") (pintype "bidirectional"))
    )
    (net (code "198") (name "unconnected-(IC3-NC-Pad77)") (class "Default")
      (node (ref "IC3") (pin "77") (pinfunction "NC_77") (pintype "bidirectional"))
    )
    (net (code "199") (name "unconnected-(IC3-NC-Pad133)") (class "Default")
      (node (ref "IC3") (pin "133") (pinfunction "NC_133") (pintype "bidirectional"))
    )
    (net (code "200") (name "unconnected-(IC3-VPP_FAST-Pad109)") (class "Default")
      (node (ref "IC3") (pin "109") (pinfunction "VPP_FAST_109") (pintype "bidirectional"))
    )
    (net (code "201") (name "unconnected-(IC7-NC-Pad4)") (class "Default")
      (node (ref "IC7") (pin "4") (pinfunction "NC_4") (pintype "no_connect"))
    )
    (net (code "202") (name "unconnected-(SD1-~{CARD}-Pad9)") (class "Default")
      (node (ref "SD1") (pin "9") (pinfunction "~{CARD}_9") (pintype "passive"))
    )
    (net (code "203") (name "unconnected-(U$2-ID-PadP$4)") (class "Default")
      (node (ref "U$2") (pin "P$4") (pinfunction "ID_P$4") (pintype "bidirectional"))
    )
    (net (code "204") (name "unconnected-(U$2-SH1-PadSH@1)") (class "Default")
      (node (ref "U$2") (pin "SH@1") (pinfunction "SH1_SH@1") (pintype "bidirectional"))
    )
  )
)
